# DDM_FOC_CostDown_Modify_X1_4.net
KiCad netlist of a schematic drawn in Altium Designer
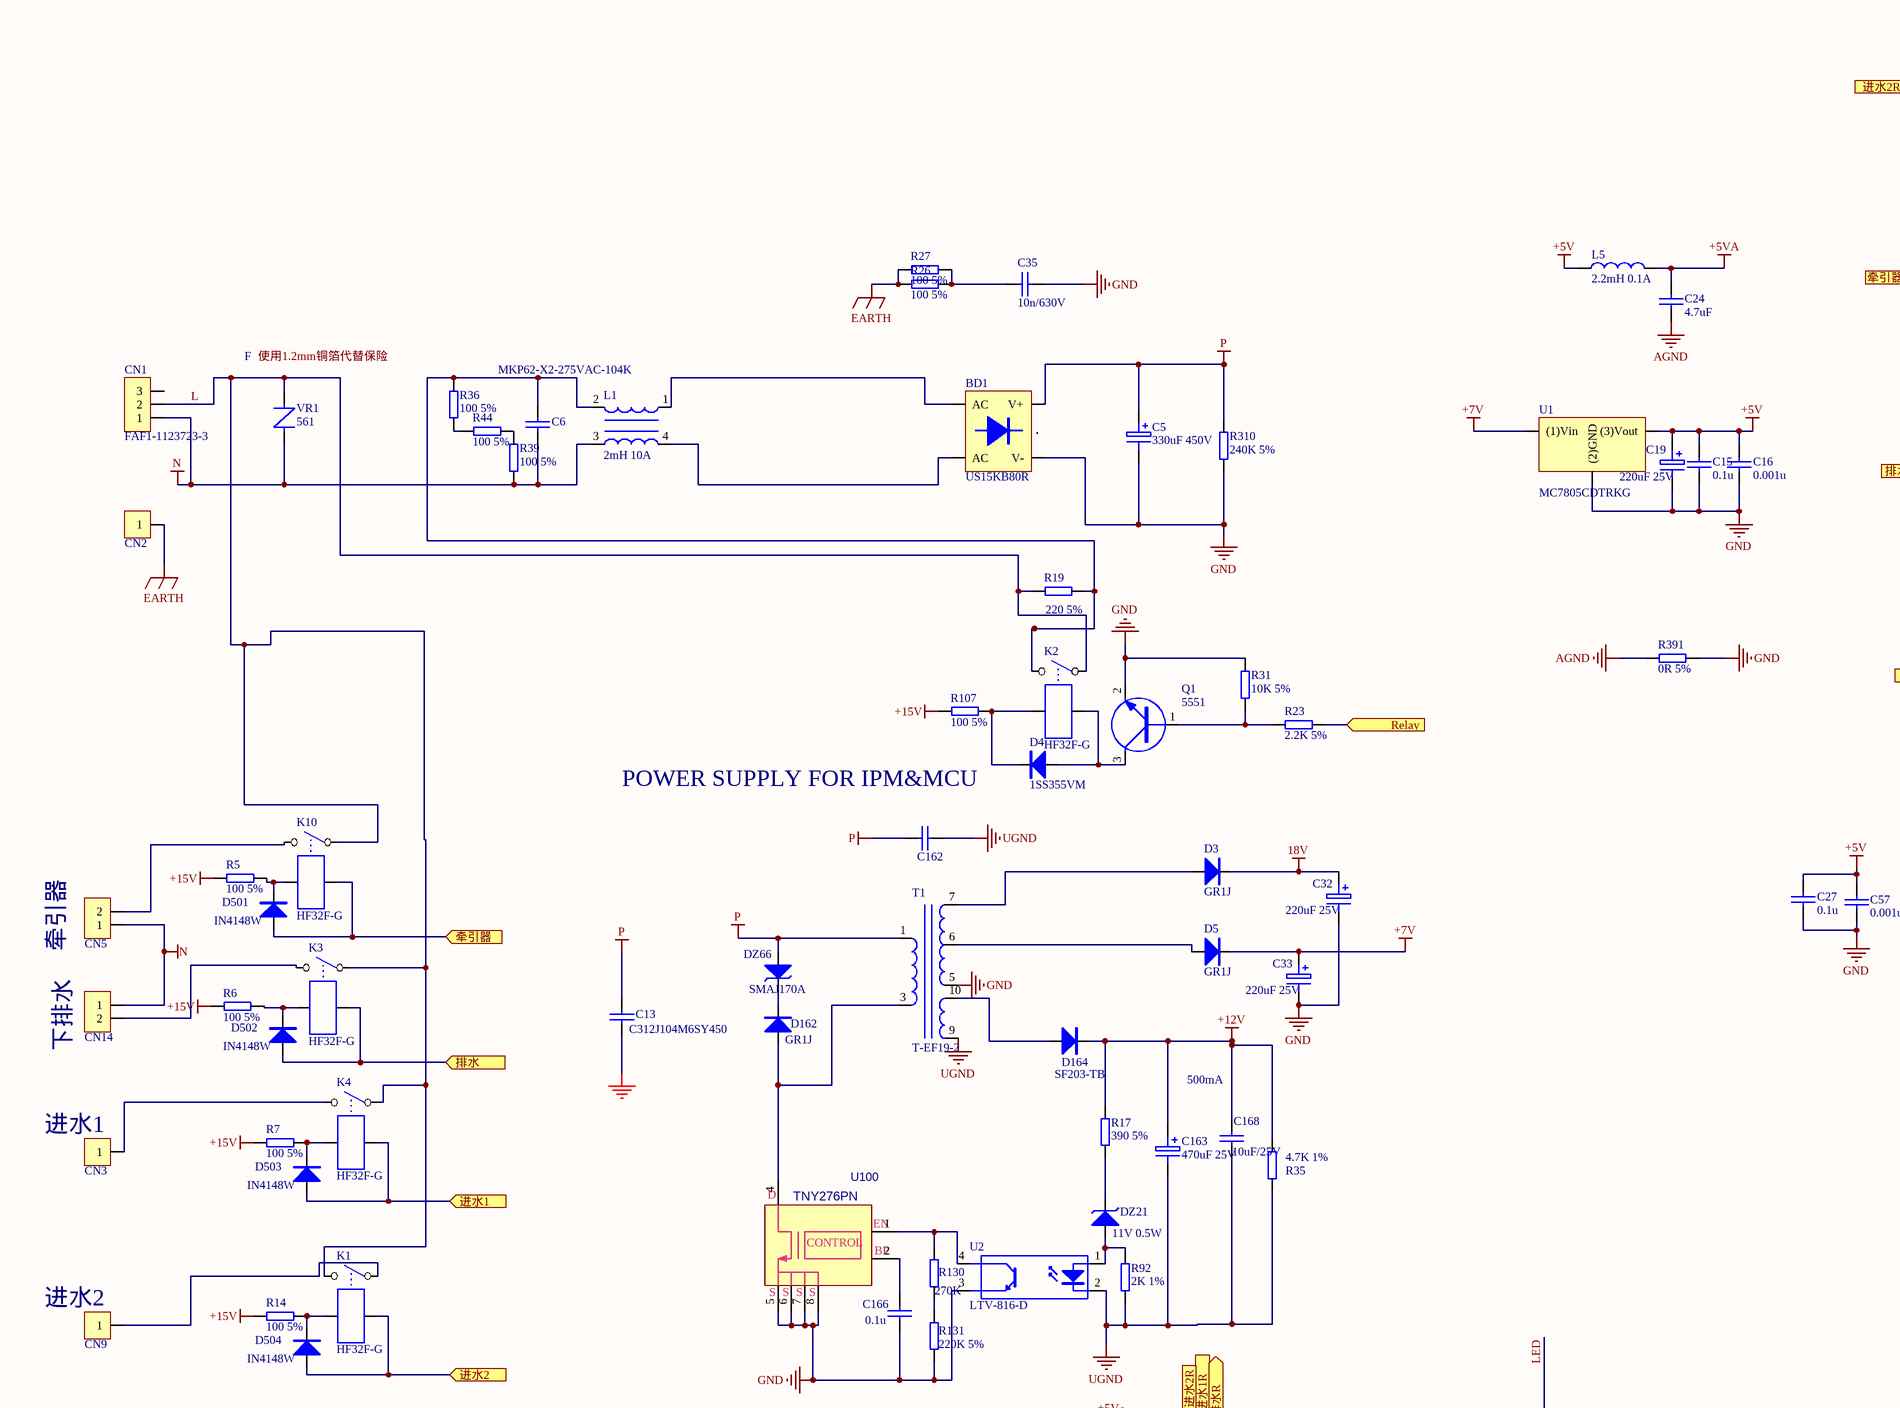
[diagram p0: DDM_FOC_CostDown_Modify_X1.4.schdoc, top left]
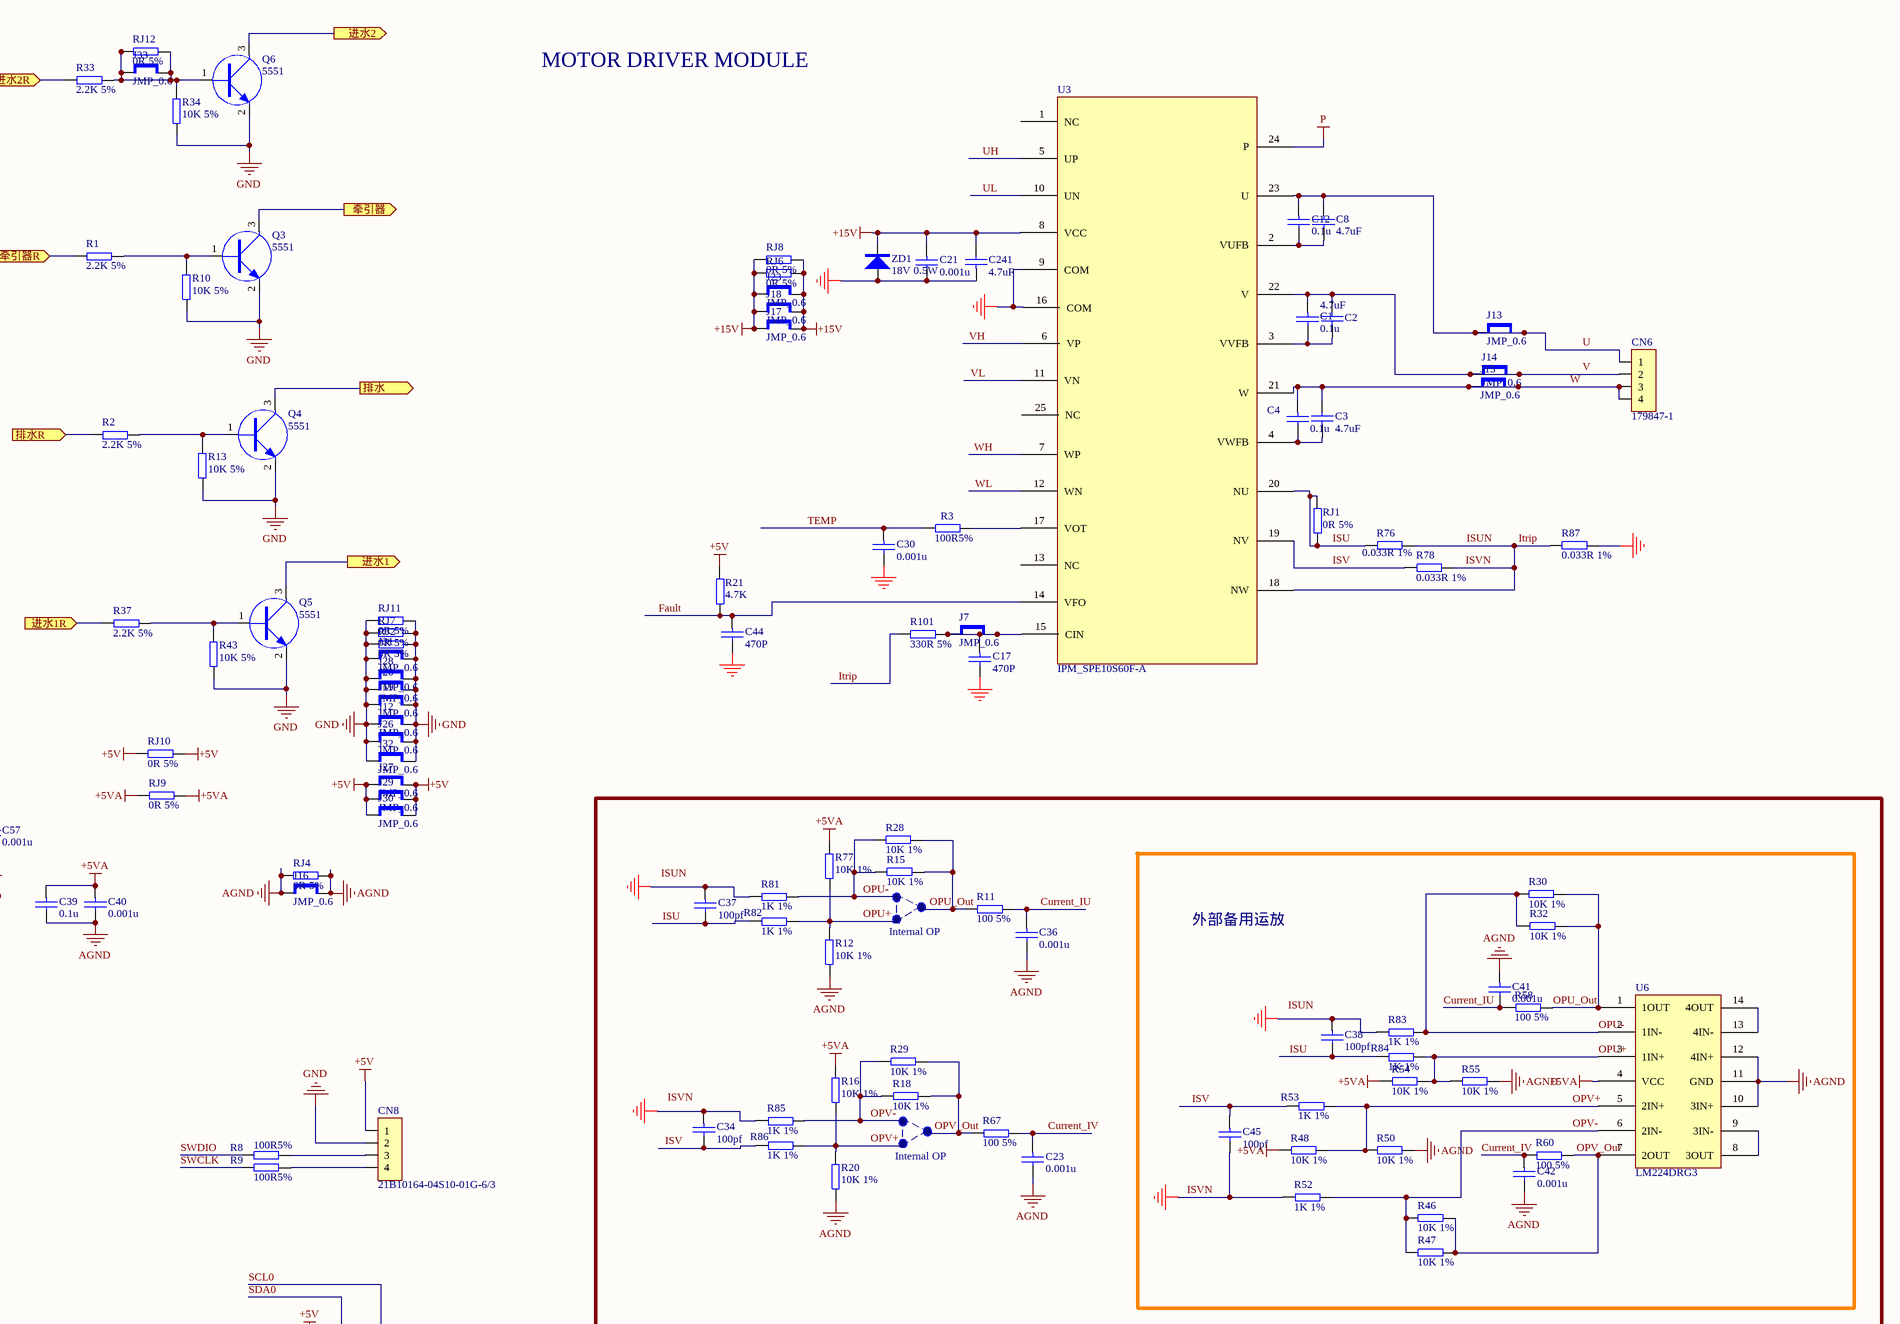
[diagram p1: DDM_FOC_CostDown_Modify_X1.4.schdoc, top right]
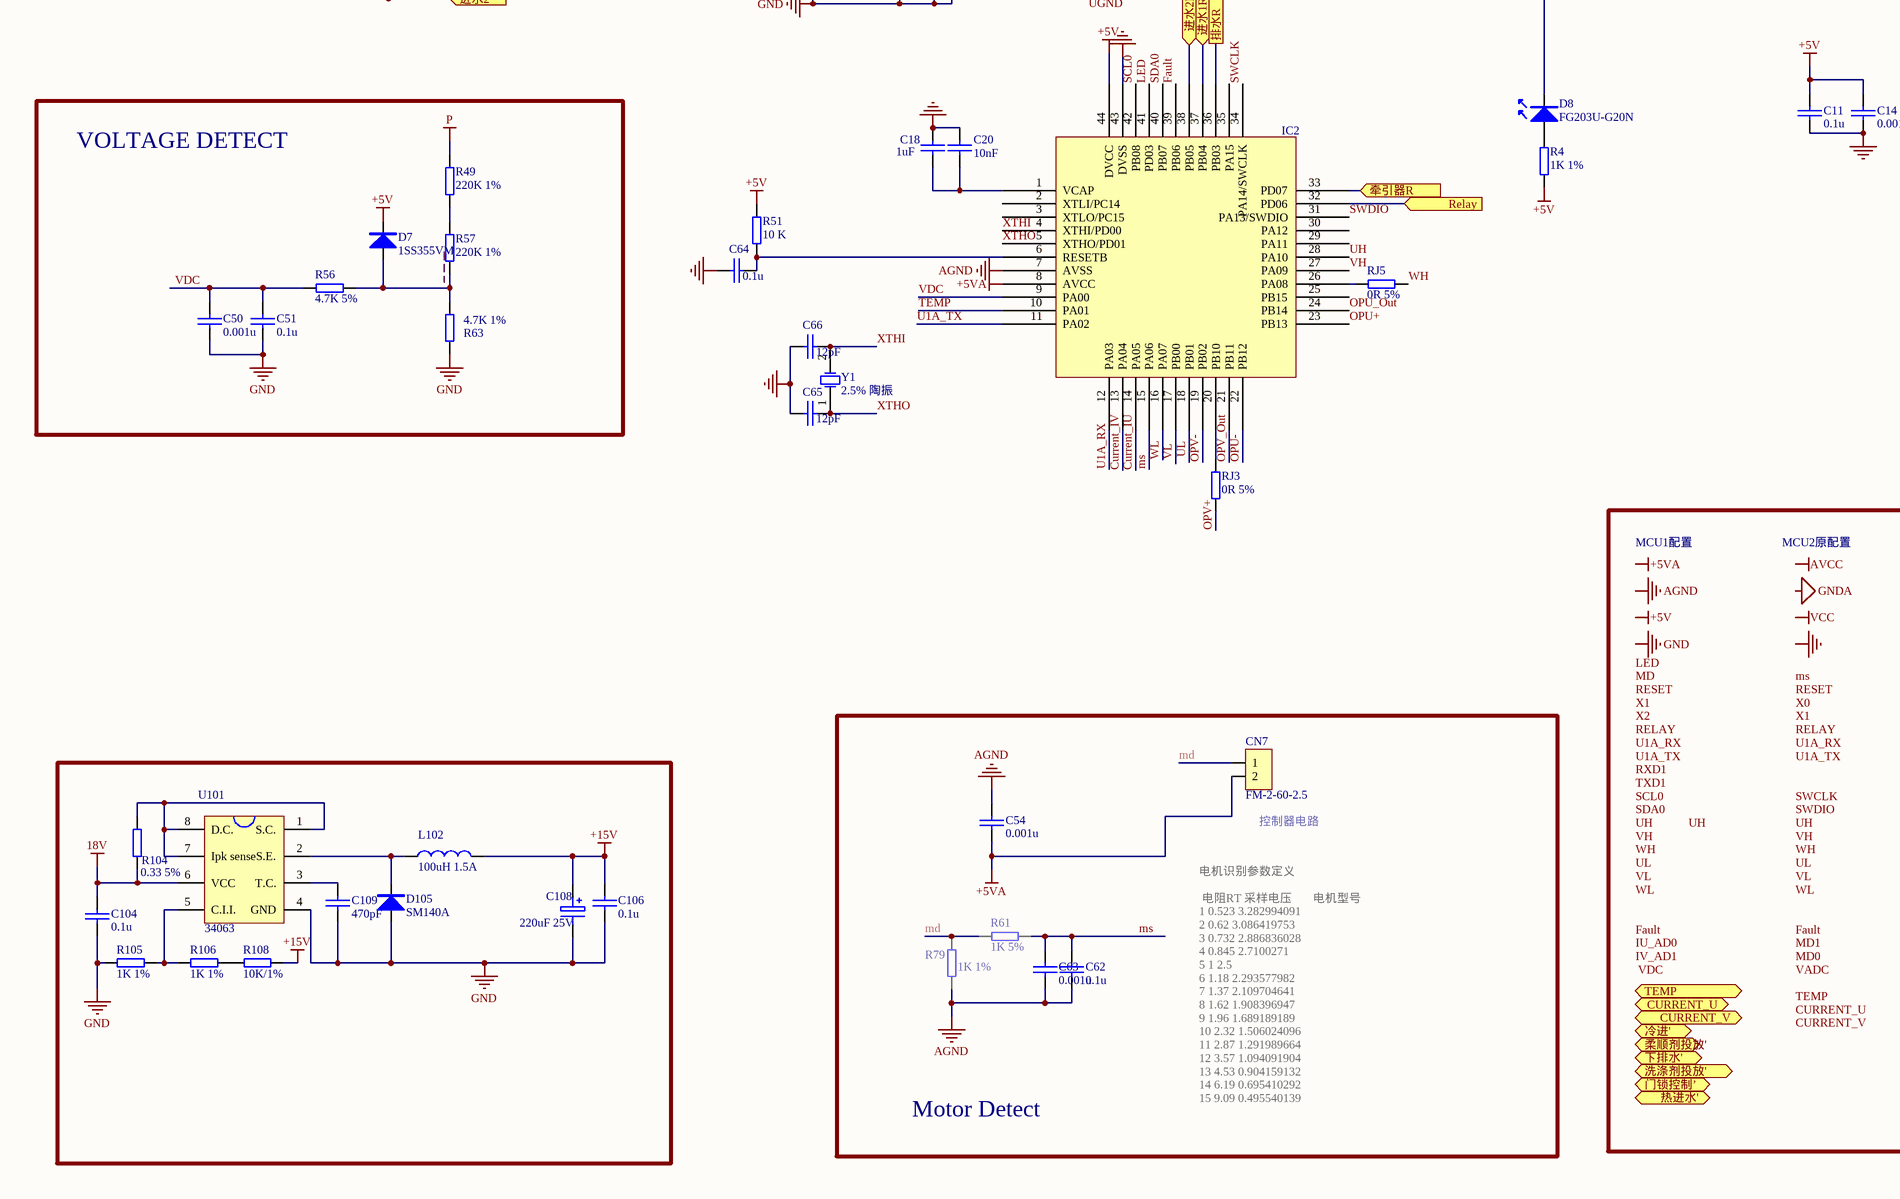
[diagram p2: DDM_FOC_CostDown_Modify_X1.4.schdoc, bottom left]
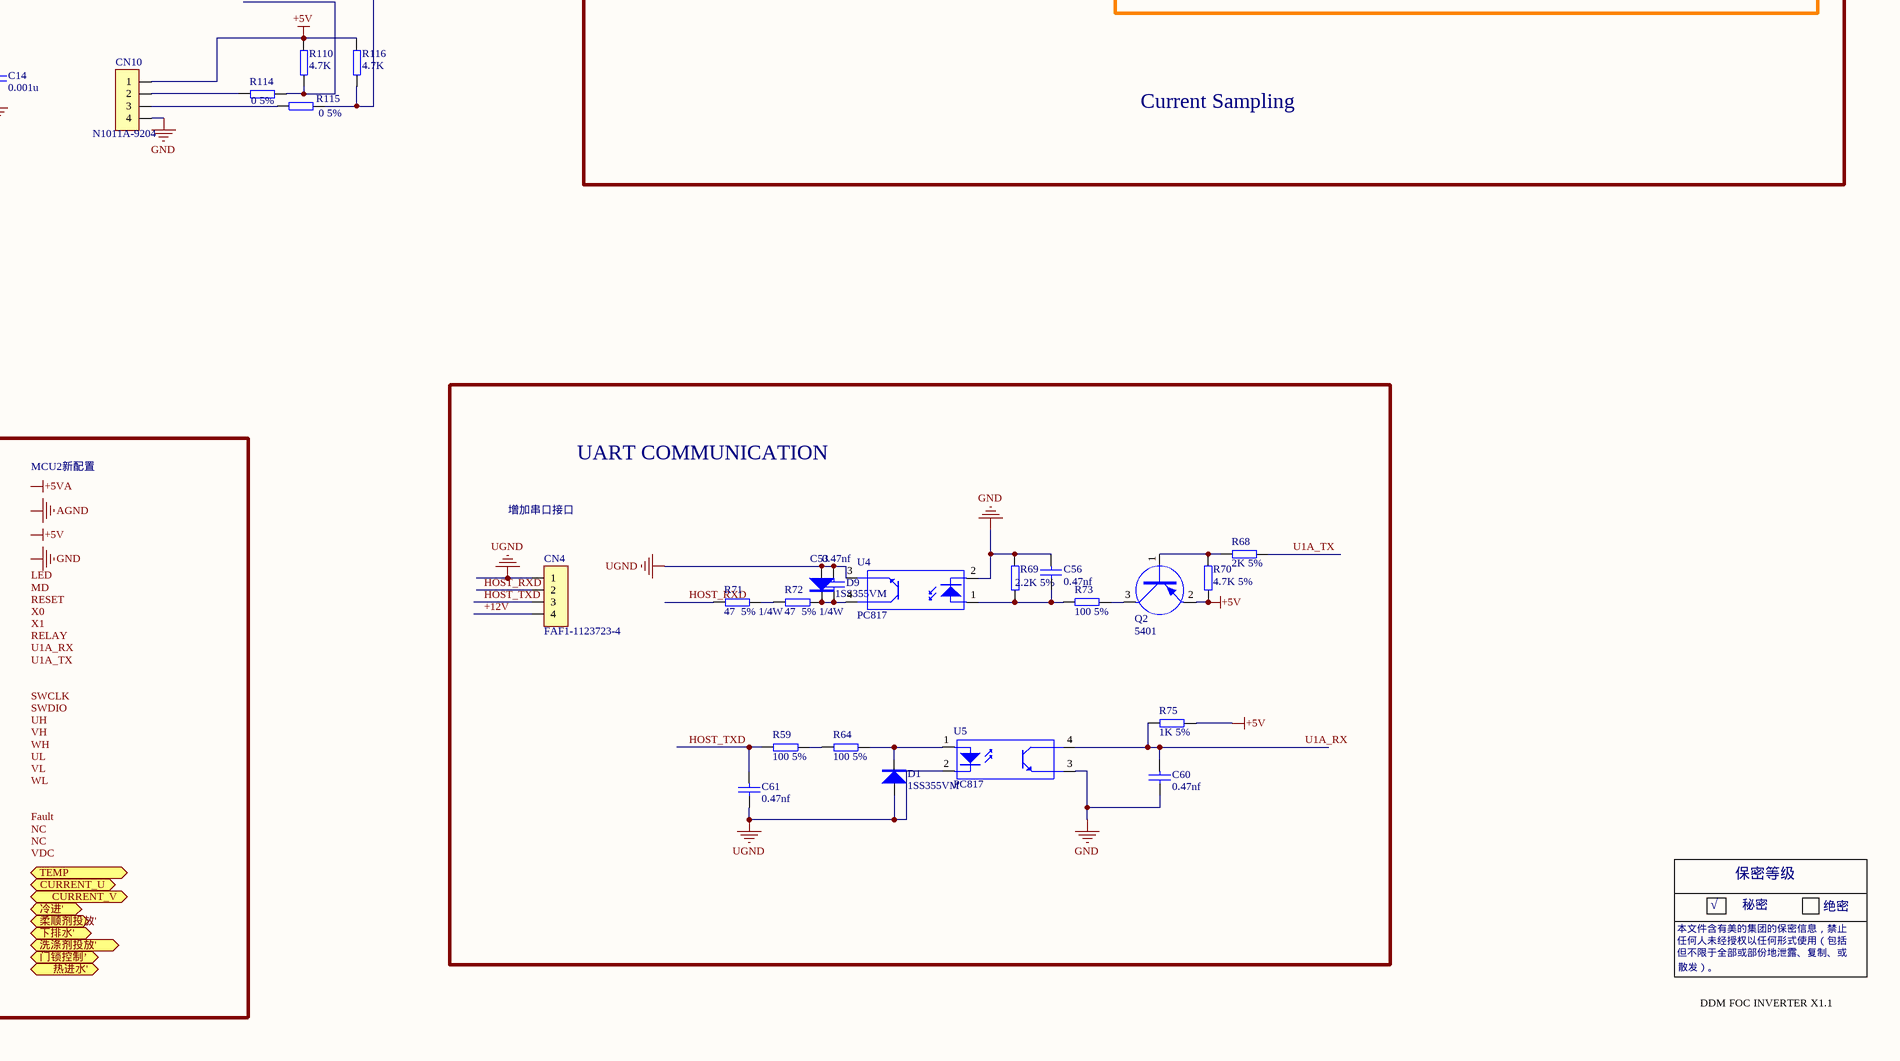
[diagram p3: DDM_FOC_CostDown_Modify_X1.4.schdoc, bottom right]

(export (version "E")
  (design (tool "Eeschema 10.0.6"))
  (components
    (comp (ref "BD1")
      (value "US15KB80R")
      (footprint "BD/D6K")
      (description "整流桥")
      (libsource (lib "sch") (part "BD_15A/800V"))
    )
    (comp (ref "C1")
      (value "0.1u")
      (footprint "C/0603")
      (description "贴片电容")
      (libsource (lib "sch") (part "C_SMD0805_104/50V_10%_X7R"))
    )
    (comp (ref "C2")
      (value "4.7uF")
      (footprint "C/1206")
      (description "瓷片电容")
      (libsource (lib "pre_sch") (part "C_SMD1206_475/25V_10%_X7R"))
    )
    (comp (ref "C3")
      (value "4.7uF")
      (footprint "C/1206")
      (description "瓷片电容")
      (libsource (lib "pre_sch") (part "C_SMD1206_475/25V_10%_X7R"))
    )
    (comp (ref "C4")
      (value "0.1u")
      (footprint "C/0603")
      (description "贴片电容")
      (libsource (lib "sch") (part "C_SMD0805_104/50V_10%_X7R"))
    )
    (comp (ref "C5")
      (value "330uF 450V")
      (footprint "E/10/35")
      (description "电解电容")
      (libsource (lib "pre_sch") (part "E_330UF/450V_85C_1"))
    )
    (comp (ref "C6")
      (value "MKP62-X2-275VAC-104K")
      (footprint "C/15/18*8.5")
      (description "薄膜电容")
      (libsource (lib "sch") (part "C_104/AC275V_10%_X2"))
    )
    (comp (ref "C8")
      (value "4.7uF")
      (footprint "C/1206")
      (description "瓷片电容")
      (libsource (lib "pre_sch") (part "C_SMD1206_475/25V_10%_X7R"))
    )
    (comp (ref "C11")
      (value "0.1u")
      (footprint "C/0603")
      (description "贴片电容")
      (libsource (lib "sch") (part "C_SMD0805_104/50V_10%_X7R"))
    )
    (comp (ref "C12")
      (value "0.1u")
      (footprint "C/0603")
      (description "贴片电容")
      (libsource (lib "sch") (part "C_SMD0805_104/50V_10%_X7R"))
    )
    (comp (ref "C13")
      (value "C312J104M6SY450")
      (footprint "C/15 /17.5*7.6")
      (description "薄膜电容C312J104M6SY450")
      (libsource (lib "pre_sch") (part "C_104/630V_5%_FILM"))
    )
    (comp (ref "C14")
      (value "0.001u")
      (footprint "C/0603")
      (description "贴片电容")
      (libsource (lib "sch") (part "C_SMD0805_104/50V_10%_X7R"))
    )
    (comp (ref "C15")
      (value "0.1u")
      (footprint "C/0603")
      (description "贴片电容")
      (libsource (lib "sch") (part "C_SMD0805_104/50V_10%_X7R"))
    )
    (comp (ref "C16")
      (value "0.001u")
      (footprint "C/0603")
      (description "贴片电容")
      (libsource (lib "sch") (part "C_SMD0805_104/50V_10%_X7R"))
    )
    (comp (ref "C17")
      (value "470P")
      (footprint "C/0603")
      (description "瓷片电容")
      (libsource (lib "sch") (part "C_SMD0603_102/50V_10%_X7R"))
    )
    (comp (ref "C18")
      (value "1uF")
      (footprint "C0603")
      (description "Ceramic Capacitor,0603")
      (libsource (lib "MyLib_Altium") (part "CAP-CC(SMD)"))
    )
    (comp (ref "C19")
      (value "220uF 25V")
      (footprint "E/5/8-@")
      (description "电解电容")
      (libsource (lib "sch") (part "E_220UF/25V_105C_L"))
    )
    (comp (ref "C20")
      (value "10nF")
      (footprint "C0603")
      (description "Ceramic Capacitor,0603")
      (libsource (lib "MyLib_Altium") (part "CAP-CC(SMD)"))
    )
    (comp (ref "C21")
      (value "0.001u")
      (footprint "C/0603")
      (description "贴片电容")
      (libsource (lib "sch") (part "C_SMD0805_104/50V_10%_X7R"))
    )
    (comp (ref "C23")
      (value "0.001u")
      (footprint "C/0603")
      (description "瓷片电容")
      (libsource (lib "sch") (part "C_SMD0603_102/50V_10%_X7R"))
    )
    (comp (ref "C24")
      (value "4.7uF")
      (footprint "C/0805")
      (description "瓷片电容")
      (libsource (lib "pre_sch") (part "C_SMD0805_475/16V_10%_X7R"))
    )
    (comp (ref "C27")
      (value "0.1u")
      (footprint "C/0603")
      (description "贴片电容")
      (libsource (lib "sch") (part "C_SMD0603_104/50V_10%_X7R"))
    )
    (comp (ref "C30")
      (value "0.001u")
      (footprint "C/0603")
      (description "瓷片电容")
      (libsource (lib "sch") (part "C_SMD0603_102/50V_10%_X7R"))
    )
    (comp (ref "C32")
      (value "220uF 25V")
      (footprint "E/5/8-@")
      (description "电解电容")
      (libsource (lib "sch") (part "E_220UF/25V_105C_L"))
    )
    (comp (ref "C33")
      (value "220uF 25V")
      (footprint "E/5/8-@")
      (description "电解电容")
      (libsource (lib "sch") (part "E_220UF/25V_105C_L"))
    )
    (comp (ref "C34")
      (value "100pf")
      (footprint "C/0603")
      (description "贴片电容")
      (libsource (lib "sch") (part "C_SMD0805_104/50V_10%_X7R"))
    )
    (comp (ref "C35")
      (value "10n/630V")
      (footprint "C/10/14.4*7")
      (description "薄膜电容")
      (libsource (lib "sch") (part "C_103/63V_10%_FILM"))
    )
    (comp (ref "C36")
      (value "0.001u")
      (footprint "C/0603")
      (description "瓷片电容")
      (libsource (lib "sch") (part "C_SMD0603_102/50V_10%_X7R"))
    )
    (comp (ref "C37")
      (value "100pf")
      (footprint "C/0603")
      (description "贴片电容")
      (libsource (lib "sch") (part "C_SMD0805_104/50V_10%_X7R"))
    )
    (comp (ref "C38")
      (value "100pf")
      (footprint "C/0603")
      (description "贴片电容")
      (libsource (lib "sch") (part "C_SMD0805_104/50V_10%_X7R"))
    )
    (comp (ref "C39")
      (value "0.1u")
      (footprint "C/0603")
      (description "贴片电容")
      (libsource (lib "sch") (part "C_SMD0805_104/50V_10%_X7R"))
    )
    (comp (ref "C40")
      (value "0.001u")
      (footprint "C/0603")
      (description "贴片电容")
      (libsource (lib "sch") (part "C_SMD0805_104/50V_10%_X7R"))
    )
    (comp (ref "C41")
      (value "0.001u")
      (footprint "C/0603")
      (description "瓷片电容")
      (libsource (lib "sch") (part "C_SMD0603_102/50V_10%_X7R"))
    )
    (comp (ref "C42")
      (value "0.001u")
      (footprint "C/0603")
      (description "瓷片电容")
      (libsource (lib "sch") (part "C_SMD0603_102/50V_10%_X7R"))
    )
    (comp (ref "C44")
      (value "470P")
      (footprint "C/0603")
      (description "贴片电容")
      (libsource (lib "sch") (part "C_SMD0805_104/50V_10%_X7R"))
    )
    (comp (ref "C45")
      (value "100pf")
      (footprint "C/0603")
      (description "贴片电容")
      (libsource (lib "sch") (part "C_SMD0805_104/50V_10%_X7R"))
    )
    (comp (ref "C50")
      (value "0.001u")
      (footprint "C/0603")
      (description "贴片电容")
      (libsource (lib "sch") (part "C_SMD0805_104/50V_10%_X7R"))
    )
    (comp (ref "C51")
      (value "0.1u")
      (footprint "C/0603")
      (description "贴片电容")
      (libsource (lib "sch") (part "C_SMD0805_104/50V_10%_X7R"))
    )
    (comp (ref "C53")
      (value "0.47nf")
      (footprint "C/0603")
      (description "瓷片电容")
      (libsource (lib "pre_sch") (part "C_SMD0603_471/50V_10%_X7R"))
    )
    (comp (ref "C54")
      (value "0.001u")
      (footprint "C/0603-SMT")
      (description "贴片电容")
      (libsource (lib "sch") (part "C_SMD0805_104/50V_10%_X7R"))
    )
    (comp (ref "C56")
      (value "0.47nf")
      (footprint "C/0603")
      (description "瓷片电容")
      (libsource (lib "pre_sch") (part "C_SMD0603_471/50V_10%_X7R"))
    )
    (comp (ref "C57")
      (value "0.001u")
      (footprint "C/0603")
      (description "贴片电容")
      (libsource (lib "sch") (part "C_SMD0805_104/50V_10%_X7R"))
    )
    (comp (ref "C60")
      (value "0.47nf")
      (footprint "C/0603")
      (description "瓷片电容")
      (libsource (lib "pre_sch") (part "C_SMD0603_471/50V_10%_X7R"))
    )
    (comp (ref "C61")
      (value "0.47nf")
      (footprint "C/0603-SMT")
      (description "瓷片电容")
      (libsource (lib "pre_sch") (part "C_SMD0603_471/50V_10%_X7R"))
    )
    (comp (ref "C62")
      (value "0.1u")
      (footprint "C/0603")
      (description "贴片电容")
      (libsource (lib "sch") (part "C_SMD0805_104/50V_10%_X7R"))
    )
    (comp (ref "C63")
      (value "0.001u")
      (footprint "C/0603-SMT")
      (description "贴片电容")
      (libsource (lib "sch") (part "C_SMD0805_104/50V_10%_X7R"))
    )
    (comp (ref "C64")
      (value "0.1u")
      (footprint "C/0603")
      (description "瓷片电容")
      (libsource (lib "*") (part "C_SMD0603_104/50V_10%_X7R"))
    )
    (comp (ref "C65")
      (value "12pF")
      (footprint "C/0603")
      (description "瓷片电容")
      (libsource (lib "*") (part "C_SMD0603_104/50V_10%_X7R"))
    )
    (comp (ref "C66")
      (value "12pF")
      (footprint "C/0603")
      (description "瓷片电容")
      (libsource (lib "*") (part "C_SMD0603_104/50V_10%_X7R"))
    )
    (comp (ref "C104")
      (value "0.1u")
      (footprint "C/0603")
      (description "贴片电容")
      (libsource (lib "SCH") (part "C_SMD0603_104/50V_10%_X7R"))
    )
    (comp (ref "C106")
      (value "0.1u")
      (footprint "C/0603")
      (description "贴片电容")
      (libsource (lib "SCH") (part "C_SMD0603_104/50V_10%_X7R"))
    )
    (comp (ref "C108")
      (value "220uF 25V")
      (footprint "E/5/8-@")
      (description "电解电容")
      (libsource (lib "sch") (part "E_220UF/25V_105C_L"))
    )
    (comp (ref "C109")
      (value "470pF")
      (footprint "C/0603")
      (description "贴片电容")
      (libsource (lib "SCH") (part "C_SMD0603_471/50V_10%"))
    )
    (comp (ref "C162")
      (value "CD12-E2GA471MYNS")
      (footprint "C/10/14.4*7")
      (description "Y1电容")
      (libsource (lib "sch") (part "C_222/AC400V_20%_Y1"))
    )
    (comp (ref "C163")
      (value "470uF 25V")
      (footprint "E/5/10-@")
      (description "电解电容")
      (libsource (lib "sch1") (part "E_470UF/25V_105C_L"))
    )
    (comp (ref "C166")
      (value "0.1u")
      (footprint "C/0603")
      (description "瓷片电容")
      (libsource (lib "sch") (part "C_SMD0603_104/50V_10%_X7R"))
    )
    (comp (ref "C168")
      (value "10uF/25V")
      (footprint "C/0805")
      (description "瓷片电容")
      (libsource (lib "sch") (part "C_SMD0805_105/25V_10%_X7R"))
    )
    (comp (ref "C241")
      (value "4.7uF")
      (footprint "C/0805")
      (description "瓷片电容")
      (libsource (lib "pre_sch") (part "C_SMD0805_475/16V_10%_X7R"))
    )
    (comp (ref "CN1")
      (value "FAF1-1123723-3")
      (footprint "CN/7.92/2")
      (description "3针插座")
      (libsource (lib "sch") (part "CN_3.96_3"))
    )
    (comp (ref "CN2")
      (value "CDW2.36-1P YE")
      (footprint "CN/CDW2.1-1P")
      (description "1针黄色插座")
      (libsource (lib "sch") (part "CN_1_01"))
    )
    (comp (ref "CN3")
      (value "CDW2.36-1P YE")
      (footprint "CN/CDW2.1-1P")
      (description "1针黄色插座")
      (libsource (lib "sch") (part "CN_1_01"))
    )
    (comp (ref "CN4")
      (value "FAF1-1123723-4")
      (footprint "CN/2.5/4-8 - 1")
      (description "4针插座")
      (libsource (lib "sch") (part "CN_3.96_4"))
    )
    (comp (ref "CN5")
      (value "PA1010")
      (footprint "CN/XH-2.1-2A")
      (description "2针插座")
      (libsource (lib "") (part "CN_8_2_05_1"))
    )
    (comp (ref "CN6")
      (value "179847-1")
      (footprint "CN/6.5/3/01")
      (description "4针插座")
      (libsource (lib "pre_sch") (part "CN_6.5_4_01"))
    )
    (comp (ref "CN7")
      (value "FM-2-60-2.5")
      (footprint "CN/2.5/2-3")
      (description "线束")
      (libsource (lib "sch") (part "CN_2.5_2"))
    )
    (comp (ref "CN8")
      (value "21B10164-04S10-01G-6/3")
      (footprint "CN/2.54/4")
      (description "单排排针4PIN")
      (libsource (lib "sch") (part "CN_2.54_4"))
    )
    (comp (ref "CN9")
      (value "CDW2.36-1P YE")
      (footprint "CN/CDW2.1-1P")
      (description "1针黄色插座")
      (libsource (lib "sch") (part "CN_1_01"))
    )
    (comp (ref "CN10")
      (value "N1011A-9204")
      (footprint "CN/2.54/4")
      (description "4针插座")
      (libsource (lib "pre_sch") (part "CN_2.5_4_6"))
    )
    (comp (ref "CN14")
      (value "PA1010")
      (footprint "CN/XH-2.1-2A")
      (description "2针插座")
      (libsource (lib "sch") (part "CN_8_2_05"))
    )
    (comp (ref "D1")
      (value "1SS355VM")
      (footprint "D/SOD-123")
      (description "贴片塑封二极管")
      (libsource (lib "pre_sch") (part "D_SMD_1SS355VM"))
    )
    (comp (ref "D3")
      (value "GR1J")
      (footprint "D/DO214AC")
      (description "二极管")
      (libsource (lib "sch1") (part "D_SMD_GR1J"))
    )
    (comp (ref "D4")
      (value "1SS355VM")
      (footprint "SOD/323")
      (description "贴片塑封二极管")
      (libsource (lib "pre_sch") (part "D_SMD_1SS355VM"))
    )
    (comp (ref "D5")
      (value "GR1J")
      (footprint "D/DO214AC")
      (description "二极管")
      (libsource (lib "sch1") (part "D_SMD_GR1J"))
    )
    (comp (ref "D7")
      (value "1SS355VM")
      (footprint "SOD/323")
      (description "贴片塑封二极管")
      (libsource (lib "pre_sch") (part "D_SMD_1SS355VM"))
    )
    (comp (ref "D8")
      (value "FG203U-G20N")
      (footprint "LED/2.54/Φ3-@")
      (description "插件发光二极管")
      (libsource (lib "sch") (part "LED_FG203U-G20N"))
    )
    (comp (ref "D9")
      (value "1SS355VM")
      (footprint "D/SOD-123")
      (description "贴片塑封二极管")
      (libsource (lib "pre_sch") (part "D_SMD_1SS355VM"))
    )
    (comp (ref "D105")
      (value "SM140A")
      (footprint "D/DO214AC")
      (description "肖特基二极管")
      (libsource (lib "pre_sch-5.11") (part "D_SMD_SM140A"))
    )
    (comp (ref "D162")
      (value "GR1J")
      (footprint "D/DO214AC")
      (description "二极管")
      (libsource (lib "sch1") (part "D_SMD_GR1J"))
    )
    (comp (ref "D164")
      (value "SF203-TB")
      (footprint "D/DO214AC")
      (description "二极管")
      (libsource (lib "sch1") (part "D_STTH1R02QRL"))
    )
    (comp (ref "D501")
      (value "IN4148W")
      (footprint "D/SOD-123")
      (description "塑封贴片二极管")
      (libsource (lib "pre_sch") (part "D_SMD_IN4148W"))
    )
    (comp (ref "D502")
      (value "IN4148W")
      (footprint "D/SOD-123")
      (description "塑封贴片二极管")
      (libsource (lib "pre_sch") (part "D_SMD_IN4148W"))
    )
    (comp (ref "D503")
      (value "IN4148W")
      (footprint "D/SOD-123")
      (description "塑封贴片二极管")
      (libsource (lib "pre_sch") (part "D_SMD_IN4148W"))
    )
    (comp (ref "D504")
      (value "IN4148W")
      (footprint "D/SOD-123")
      (description "塑封贴片二极管")
      (libsource (lib "pre_sch") (part "D_SMD_IN4148W"))
    )
    (comp (ref "DZ21")
      (value "11V 0.5W")
      (footprint "D/SOD80")
      (description "稳压二极管")
      (libsource (lib "sch1") (part "DZ_SMD_11V/0.5W"))
    )
    (comp (ref "DZ66")
      (value "SMAJ170A")
      (footprint "D/DO214AC")
      (description "TVS")
      (libsource (lib "sch1") (part "D_SMD_SMAJ170A"))
    )
    (comp (ref "IC2") (value "HC32F030") (libsource (lib "LQFP44") (part "HC32F030H8TA_LQFP44")))
    (comp (ref "J7")
      (value "JMP_0.6")
      (footprint "J/10-@")
      (description "跳线")
      (libsource (lib "sch") (part "J_D0.6"))
    )
    (comp (ref "J12")
      (value "JMP_0.6")
      (footprint "J/7-@")
      (description "跳线")
      (libsource (lib "sch") (part "J_D0.6"))
    )
    (comp (ref "J13")
      (value "JMP_0.6")
      (footprint "J/14-@")
      (description "跳线")
      (libsource (lib "sch") (part "J_D0.6"))
    )
    (comp (ref "J14")
      (value "JMP_0.6")
      (footprint "J/14-@")
      (description "跳线")
      (libsource (lib "sch") (part "J_D0.6"))
    )
    (comp (ref "J15")
      (value "JMP_0.6")
      (footprint "J/16-@")
      (description "跳线")
      (libsource (lib "sch") (part "J_D0.6"))
    )
    (comp (ref "J16")
      (value "JMP_0.6")
      (footprint "J/9-@")
      (description "跳线")
      (libsource (lib "sch") (part "J_D0.6"))
    )
    (comp (ref "J17")
      (value "JMP_0.6")
      (footprint "J/8-@")
      (description "跳线")
      (libsource (lib "sch") (part "J_D0.6"))
    )
    (comp (ref "J18")
      (value "JMP_0.6")
      (footprint "J/6-@")
      (description "跳线")
      (libsource (lib "sch") (part "J_D0.6"))
    )
    (comp (ref "J19")
      (value "JMP_0.6")
      (footprint "J/15-@")
      (description "跳线")
      (libsource (lib "sch") (part "J_D0.6"))
    )
    (comp (ref "J20")
      (value "JMP_0.6")
      (footprint "J/17-@")
      (description "跳线")
      (libsource (lib "sch") (part "J_D0.6"))
    )
    (comp (ref "J23")
      (value "JMP_0.6")
      (footprint "J/18-@")
      (description "跳线")
      (libsource (lib "sch") (part "J_D0.6"))
    )
    (comp (ref "J26")
      (value "JMP_0.6")
      (footprint "J/9-@")
      (description "跳线")
      (libsource (lib "sch") (part "J_D0.6"))
    )
    (comp (ref "J27")
      (value "JMP_0.6")
      (footprint "J/9-@")
      (description "跳线")
      (libsource (lib "sch") (part "J_D0.6"))
    )
    (comp (ref "J28")
      (value "JMP_0.6")
      (footprint "J/12-@")
      (description "跳线")
      (libsource (lib "sch") (part "J_D0.6"))
    )
    (comp (ref "J29")
      (value "JMP_0.6")
      (footprint "J/7-@")
      (description "跳线")
      (libsource (lib "sch") (part "J_D0.6"))
    )
    (comp (ref "J30")
      (value "JMP_0.6")
      (footprint "J/8-@")
      (description "跳线")
      (libsource (lib "sch") (part "J_D0.6"))
    )
    (comp (ref "J31")
      (value "JMP_0.6")
      (footprint "J/7-@")
      (description "跳线")
      (libsource (lib "sch") (part "J_D0.6"))
    )
    (comp (ref "J32")
      (value "JMP_0.6")
      (footprint "J/12-@")
      (description "跳线")
      (libsource (lib "sch") (part "J_D0.6"))
    )
    (comp (ref "J33")
      (value "JMP_0.6")
      (footprint "J/6-@")
      (description "跳线")
      (libsource (lib "sch") (part "J_D0.6"))
    )
    (comp (ref "K1")
      (value "HF32F-G")
      (footprint "RY/HF32")
      (description "继电器")
      (libsource (lib "sch") (part "RY_SPST_HF32F-G/012-HS"))
    )
    (comp (ref "K2")
      (value "HF32F-G")
      (footprint "RY/HF32")
      (description "继电器")
      (libsource (lib "sch") (part "RY_SPST_HF32F-G/012-HS"))
    )
    (comp (ref "K3")
      (value "HF32F-G")
      (footprint "RY/HF32")
      (description "继电器")
      (libsource (lib "sch") (part "RY_SPST_HF32F-G/012-HS"))
    )
    (comp (ref "K4")
      (value "HF32F-G")
      (footprint "RY/HF32")
      (description "继电器")
      (libsource (lib "sch") (part "RY_SPST_HF32F-G/012-HS"))
    )
    (comp (ref "K10")
      (value "HF32F-G")
      (footprint "RY/HF32")
      (description "继电器")
      (libsource (lib "sch") (part "RY_SPST_HF32F-G/012-HS"))
    )
    (comp (ref "L1")
      (value "2mH 10A")
      (footprint "L/18*21")
      (description "电感")
      (libsource (lib "pre_sch") (part "L_10A_2MH"))
    )
    (comp (ref "L5")
      (value "2.2mH 0.1A")
      (footprint "L/15/0410@")
      (description "电感")
      (libsource (lib "pre_sch") (part "L_0.1A_1MH"))
    )
    (comp (ref "L102")
      (value "100uH 1.5A")
      (footprint "L/5/11")
      (description "电感")
      (libsource (lib "pre_sch-5.11") (part "L_1.5A_100uH"))
    )
    (comp (ref "Q1")
      (value "5551")
      (footprint "Q/SOT23")
      (description "三极管")
      (libsource (lib "sch") (part "Q_N_MMBT5551_SOT23"))
    )
    (comp (ref "Q2")
      (value "5401")
      (footprint "Q/SOT23")
      (description "三极管")
      (libsource (lib "sch") (part "Q_P_MMBT5401_SOT23"))
    )
    (comp (ref "Q3")
      (value "5551")
      (footprint "Q/SOT23")
      (description "三极管")
      (libsource (lib "sch") (part "Q_N_MMBT5551_SOT23"))
    )
    (comp (ref "Q4")
      (value "5551")
      (footprint "Q/SOT23")
      (description "三极管")
      (libsource (lib "sch") (part "Q_N_MMBT5551_SOT23"))
    )
    (comp (ref "Q5")
      (value "5551")
      (footprint "Q/SOT23")
      (description "三极管")
      (libsource (lib "sch") (part "Q_N_MMBT5551_SOT23"))
    )
    (comp (ref "Q6")
      (value "5551")
      (footprint "Q/SOT23")
      (description "三极管")
      (libsource (lib "sch") (part "Q_N_MMBT5551_SOT23"))
    )
    (comp (ref "R1")
      (value "2.2K 5%")
      (footprint "R/0805")
      (description "电阻")
      (libsource (lib "sch") (part "R_SMD_0805_2.2K"))
    )
    (comp (ref "R2")
      (value "2.2K 5%")
      (footprint "R/0805")
      (description "电阻")
      (libsource (lib "sch") (part "R_SMD_0805_2.2K"))
    )
    (comp (ref "R3")
      (value "100R5%")
      (footprint "R/0805")
      (description "电阻")
      (libsource (lib "sch") (part "R_SMD_1206_0R"))
    )
    (comp (ref "R4")
      (value "1K 1%")
      (footprint "R/0805")
      (description "贴片电阻")
      (libsource (lib "sch") (part "R_SMD_0805_1K_1%"))
    )
    (comp (ref "R5")
      (value "100 5%")
      (footprint "R/1206")
      (description "电阻")
      (libsource (lib "sch") (part "R_SMD_1206_100"))
    )
    (comp (ref "R6")
      (value "100 5%")
      (footprint "R/1206")
      (description "电阻")
      (libsource (lib "sch") (part "R_SMD_1206_100"))
    )
    (comp (ref "R7")
      (value "100 5%")
      (footprint "R/1206")
      (description "电阻")
      (libsource (lib "sch") (part "R_SMD_1206_100"))
    )
    (comp (ref "R8")
      (value "100R5%")
      (footprint "R/0805")
      (description "电阻")
      (libsource (lib "sch") (part "R_SMD_1206_0R"))
    )
    (comp (ref "R9")
      (value "100R5%")
      (footprint "R/0805")
      (description "电阻")
      (libsource (lib "sch") (part "R_SMD_1206_0R"))
    )
    (comp (ref "R10")
      (value "10K 5%")
      (footprint "R/0805")
      (description "电阻")
      (libsource (lib "sch") (part "R_SMD_0805_10K"))
    )
    (comp (ref "R11")
      (value "100 5%")
      (footprint "R/0805")
      (description "贴片电阻")
      (libsource (lib "sch") (part "R_SMD_0805_100"))
    )
    (comp (ref "R12")
      (value "10K 1%")
      (footprint "R/0805")
      (description "电阻")
      (libsource (lib "sch") (part "R_SMD_0805_24.9K_1%"))
    )
    (comp (ref "R13")
      (value "10K 5%")
      (footprint "R/0805")
      (description "电阻")
      (libsource (lib "sch") (part "R_SMD_0805_10K"))
    )
    (comp (ref "R14")
      (value "100 5%")
      (footprint "R/1206")
      (description "电阻")
      (libsource (lib "sch") (part "R_SMD_1206_100"))
    )
    (comp (ref "R15")
      (value "10K 1%")
      (footprint "R/0805")
      (description "电阻")
      (libsource (lib "sch") (part "R_SMD_0805_24.9K_1%"))
    )
    (comp (ref "R16")
      (value "10K 1%")
      (footprint "R/0805")
      (description "电阻")
      (libsource (lib "sch") (part "R_SMD_0805_24.9K_1%"))
    )
    (comp (ref "R17")
      (value "390 5%")
      (footprint "R/1206")
      (description "电阻")
      (libsource (lib "sch") (part "R_SMD_1206_330"))
    )
    (comp (ref "R18")
      (value "10K 1%")
      (footprint "R/0805")
      (description "电阻")
      (libsource (lib "sch") (part "R_SMD_0805_24.9K_1%"))
    )
    (comp (ref "R19")
      (value "220 5%")
      (footprint "R/7.5/PTC")
      (description "电阻")
      (libsource (lib "pre_sch") (part "R_220_5%_2W"))
    )
    (comp (ref "R20")
      (value "10K 1%")
      (footprint "R/0805")
      (description "电阻")
      (libsource (lib "sch") (part "R_SMD_0805_24.9K_1%"))
    )
    (comp (ref "R21") (value "4.7K") (footprint "R/0805") (libsource (lib "*") (part "RES")))
    (comp (ref "R23")
      (value "2.2K 5%")
      (footprint "R/0805")
      (description "电阻")
      (libsource (lib "sch") (part "R_SMD_0805_2.2K"))
    )
    (comp (ref "R26")
      (value "100 5%")
      (footprint "R/1206")
      (description "电阻")
      (libsource (lib "sch") (part "R_SMD_1206_100"))
    )
    (comp (ref "R27")
      (value "100 5%")
      (footprint "R/1206")
      (description "电阻")
      (libsource (lib "sch") (part "R_SMD_1206_100"))
    )
    (comp (ref "R28")
      (value "10K 1%")
      (footprint "R/0805")
      (description "电阻")
      (libsource (lib "sch") (part "R_SMD_0805_24.9K_1%"))
    )
    (comp (ref "R29")
      (value "10K 1%")
      (footprint "R/0805")
      (description "电阻")
      (libsource (lib "sch") (part "R_SMD_0805_24.9K_1%"))
    )
    (comp (ref "R30")
      (value "10K 1%")
      (footprint "R/0805")
      (description "电阻")
      (libsource (lib "sch") (part "R_SMD_0805_24.9K_1%"))
    )
    (comp (ref "R31")
      (value "10K 5%")
      (footprint "R/0805")
      (description "电阻")
      (libsource (lib "sch") (part "R_SMD_0805_10K"))
    )
    (comp (ref "R32")
      (value "10K 1%")
      (footprint "R/0805")
      (description "电阻")
      (libsource (lib "sch") (part "R_SMD_0805_24.9K_1%"))
    )
    (comp (ref "R33")
      (value "2.2K 5%")
      (footprint "R/0805")
      (description "电阻")
      (libsource (lib "sch") (part "R_SMD_0805_2.2K"))
    )
    (comp (ref "R34")
      (value "10K 5%")
      (footprint "R/0805")
      (description "电阻")
      (libsource (lib "sch") (part "R_SMD_0805_10K"))
    )
    (comp (ref "R35")
      (value "4.7K 1%")
      (footprint "R/0805")
      (description "电阻")
      (libsource (lib "sch") (part "R_SMD_0805_2.43K_1%"))
    )
    (comp (ref "R36")
      (value "100 5%")
      (footprint "R/1206")
      (description "电阻")
      (libsource (lib "sch") (part "R_SMD_1206_100"))
    )
    (comp (ref "R37")
      (value "2.2K 5%")
      (footprint "R/0805")
      (description "电阻")
      (libsource (lib "sch") (part "R_SMD_0805_2.2K"))
    )
    (comp (ref "R39")
      (value "100 5%")
      (footprint "R/1206")
      (description "电阻")
      (libsource (lib "sch") (part "R_SMD_1206_100"))
    )
    (comp (ref "R43")
      (value "10K 5%")
      (footprint "R/0805")
      (description "电阻")
      (libsource (lib "sch") (part "R_SMD_0805_10K"))
    )
    (comp (ref "R44")
      (value "100 5%")
      (footprint "R/1206")
      (description "电阻")
      (libsource (lib "sch") (part "R_SMD_1206_100"))
    )
    (comp (ref "R46")
      (value "10K 1%")
      (footprint "R/0805")
      (description "电阻")
      (libsource (lib "sch") (part "R_SMD_0805_24.9K_1%"))
    )
    (comp (ref "R47")
      (value "10K 1%")
      (footprint "R/0805")
      (description "电阻")
      (libsource (lib "sch") (part "R_SMD_0805_24.9K_1%"))
    )
    (comp (ref "R48")
      (value "10K 1%")
      (footprint "R/0805")
      (description "电阻")
      (libsource (lib "sch") (part "R_SMD_0805_24.9K_1%"))
    )
    (comp (ref "R49")
      (value "220K 1%")
      (footprint "R/1206")
      (description "电阻")
      (libsource (lib "pre_sch") (part "R_SMD_1206_220K_1%"))
    )
    (comp (ref "R50")
      (value "10K 1%")
      (footprint "R/0805")
      (description "电阻")
      (libsource (lib "sch") (part "R_SMD_0805_24.9K_1%"))
    )
    (comp (ref "R51")
      (value "10 K")
      (footprint "R/0805")
      (description "电阻")
      (libsource (lib "*") (part "R_SMD_0805_3.3K"))
    )
    (comp (ref "R52")
      (value "1K 1%")
      (footprint "R/0805")
      (description "电阻")
      (libsource (lib "sch") (part "R_SMD_0805_3.09K_1%"))
    )
    (comp (ref "R53")
      (value "1K 1%")
      (footprint "R/0805")
      (description "电阻")
      (libsource (lib "sch") (part "R_SMD_0805_3.09K_1%"))
    )
    (comp (ref "R54")
      (value "10K 1%")
      (footprint "R/0805")
      (description "电阻")
      (libsource (lib "sch") (part "R_SMD_0805_24.9K_1%"))
    )
    (comp (ref "R55")
      (value "10K 1%")
      (footprint "R/0805")
      (description "电阻")
      (libsource (lib "sch") (part "R_SMD_0805_24.9K_1%"))
    )
    (comp (ref "R56")
      (value "4.7K 5%")
      (footprint "R/0805")
      (description "电阻")
      (libsource (lib "sch") (part "R_SMD_0805_4.7K"))
    )
    (comp (ref "R57")
      (value "220K 1%")
      (footprint "R/1206")
      (description "电阻")
      (libsource (lib "pre_sch") (part "R_SMD_1206_220K_1%"))
    )
    (comp (ref "R58")
      (value "100 5%")
      (footprint "R/0805")
      (description "贴片电阻")
      (libsource (lib "sch") (part "R_SMD_0805_100"))
    )
    (comp (ref "R59")
      (value "100 5%")
      (footprint "R/1206")
      (description "电阻")
      (libsource (lib "sch") (part "R_SMD_1206_100"))
    )
    (comp (ref "R60")
      (value "100 5%")
      (footprint "R/0805")
      (description "贴片电阻")
      (libsource (lib "sch") (part "R_SMD_0805_100"))
    )
    (comp (ref "R61")
      (value "1K 5%")
      (footprint "R/0805")
      (description "电阻")
      (libsource (lib "sch") (part "R_SMD_0805_1K"))
    )
    (comp (ref "R63")
      (value "4.7K 1%")
      (footprint "R/0805")
      (description "电阻")
      (libsource (lib "sch") (part "R_SMD_0805_2.43K_1%"))
    )
    (comp (ref "R64")
      (value "100 5%")
      (footprint "R/1206")
      (description "电阻")
      (libsource (lib "sch") (part "R_SMD_1206_100"))
    )
    (comp (ref "R67")
      (value "100 5%")
      (footprint "R/0805")
      (description "贴片电阻")
      (libsource (lib "sch") (part "R_SMD_0805_100"))
    )
    (comp (ref "R68")
      (value "2K 5%")
      (footprint "R/0805")
      (description "电阻")
      (libsource (lib "sch") (part "R_SMD_0805_2.2K"))
    )
    (comp (ref "R69")
      (value "2.2K 5%")
      (footprint "R/0805")
      (description "电阻")
      (libsource (lib "sch") (part "R_SMD_0805_2.2K"))
    )
    (comp (ref "R70")
      (value "4.7K 5%")
      (footprint "R/0805")
      (description "电阻")
      (libsource (lib "sch") (part "R_SMD_0805_4.7K"))
    )
    (comp (ref "R71")
      (value "47  5% 1/4W")
      (footprint "R/1206")
      (description "电阻")
      (libsource (lib "pre_sch") (part "R_SMD_1206_47"))
    )
    (comp (ref "R72")
      (value "47  5% 1/4W")
      (footprint "R/1206")
      (description "电阻")
      (libsource (lib "pre_sch") (part "R_SMD_1206_47"))
    )
    (comp (ref "R73")
      (value "100 5%")
      (footprint "R/1206")
      (description "电阻")
      (libsource (lib "sch") (part "R_SMD_1206_100"))
    )
    (comp (ref "R75")
      (value "1K 5%")
      (footprint "R/0805")
      (description "电阻")
      (libsource (lib "sch") (part "R_SMD_0805_330"))
    )
    (comp (ref "R76")
      (value "0.033R 1%")
      (footprint "R/2512")
      (description "电阻")
      (libsource (lib "pre_sch") (part "R_SMD_2512_150K"))
    )
    (comp (ref "R77")
      (value "10K 1%")
      (footprint "R/0805")
      (description "电阻")
      (libsource (lib "sch") (part "R_SMD_0805_24.9K_1%"))
    )
    (comp (ref "R78")
      (value "0.033R 1%")
      (footprint "R/2512")
      (description "电阻")
      (libsource (lib "pre_sch") (part "R_SMD_2512_150K"))
    )
    (comp (ref "R79")
      (value "1K 1%")
      (footprint "R/0805")
      (description "电阻")
      (libsource (lib "sch") (part "R_SMD_0805_1K"))
    )
    (comp (ref "R81")
      (value "1K 1%")
      (footprint "R/0805")
      (description "电阻")
      (libsource (lib "sch") (part "R_SMD_0805_3.09K_1%"))
    )
    (comp (ref "R82")
      (value "1K 1%")
      (footprint "R/0805")
      (description "电阻")
      (libsource (lib "sch") (part "R_SMD_0805_3.09K_1%"))
    )
    (comp (ref "R83")
      (value "1K 1%")
      (footprint "R/0805")
      (description "电阻")
      (libsource (lib "sch") (part "R_SMD_0805_3.09K_1%"))
    )
    (comp (ref "R84")
      (value "1K 1%")
      (footprint "R/0805")
      (description "电阻")
      (libsource (lib "sch") (part "R_SMD_0805_3.09K_1%"))
    )
    (comp (ref "R85")
      (value "1K 1%")
      (footprint "R/0805")
      (description "电阻")
      (libsource (lib "sch") (part "R_SMD_0805_3.09K_1%"))
    )
    (comp (ref "R86")
      (value "1K 1%")
      (footprint "R/0805")
      (description "电阻")
      (libsource (lib "sch") (part "R_SMD_0805_3.09K_1%"))
    )
    (comp (ref "R87")
      (value "0.033R 1%")
      (footprint "R/2512")
      (description "电阻")
      (libsource (lib "pre_sch") (part "R_SMD_2512_150K"))
    )
    (comp (ref "R92")
      (value "2K 1%")
      (footprint "R/0805")
      (description "电阻")
      (libsource (lib "sch") (part "R_SMD_0805_2K_1%"))
    )
    (comp (ref "R101")
      (value "330R 5%")
      (footprint "R/0805")
      (description "电阻")
      (libsource (lib "sch") (part "R_SMD_0805_1K_1%"))
    )
    (comp (ref "R104")
      (value "0.33 5%")
      (footprint "R/1206")
      (description "电阻")
      (libsource (lib "sch-5.11") (part "R_SMD_1206_330"))
    )
    (comp (ref "R105")
      (value "1K 1%")
      (footprint "R/0805")
      (description "电阻")
      (libsource (lib "sch") (part "R_SMD_0805_1K_1%"))
    )
    (comp (ref "R106")
      (value "1K 1%")
      (footprint "R/0805")
      (description "电阻")
      (libsource (lib "sch") (part "R_SMD_0805_1K_1%"))
    )
    (comp (ref "R107")
      (value "100 5%")
      (footprint "R/1206")
      (description "电阻")
      (libsource (lib "sch") (part "R_SMD_1206_100"))
    )
    (comp (ref "R108") (value "10K/1%") (footprint "R/0805") (libsource (lib "*") (part "RES")))
    (comp (ref "R110") (value "4.7K") (footprint "R/0805") (libsource (lib "*") (part "RES")))
    (comp (ref "R114") (value "0 5%") (footprint "R/0805") (libsource (lib "*") (part "RES")))
    (comp (ref "R115") (value "0 5%") (footprint "R/0805") (libsource (lib "*") (part "RES")))
    (comp (ref "R116") (value "4.7K") (footprint "R/0805") (libsource (lib "*") (part "RES")))
    (comp (ref "R130")
      (value "270K")
      (footprint "R/0805")
      (description "贴片电阻")
      (libsource (lib "sch") (part "R_SMD_0805_270K_1%"))
    )
    (comp (ref "R131")
      (value "220K 5%")
      (footprint "R/0805")
      (description "电阻")
      (libsource (lib "pre_sch") (part "R_SMD_0805_220K"))
    )
    (comp (ref "R310")
      (value "240K 5%")
      (footprint "R/2512")
      (description "电阻")
      (libsource (lib "sch") (part "R_SMD_0805_10K"))
    )
    (comp (ref "R391")
      (value "0R 5%")
      (footprint "J/1206")
      (description "电阻")
      (libsource (lib "sch") (part "R_SMD_1206_0R"))
    )
    (comp (ref "RJ1")
      (value "0R 5%")
      (footprint "J/1206")
      (description "贴片电阻")
      (libsource (lib "sch") (part "R_SMD_1206_0R"))
    )
    (comp (ref "RJ2")
      (value "0R 5%")
      (footprint "J/1206")
      (description "贴片电阻")
      (libsource (lib "sch") (part "R_SMD_1206_0R"))
    )
    (comp (ref "RJ3")
      (value "0R 5%")
      (footprint "J/1206")
      (description "贴片电阻")
      (libsource (lib "sch") (part "R_SMD_1206_0R"))
    )
    (comp (ref "RJ4")
      (value "0R 5%")
      (footprint "J/1206")
      (description "贴片电阻")
      (libsource (lib "sch") (part "R_SMD_1206_0R"))
    )
    (comp (ref "RJ5")
      (value "0R 5%")
      (footprint "J/1206")
      (description "贴片电阻")
      (libsource (lib "sch") (part "R_SMD_1206_0R"))
    )
    (comp (ref "RJ6")
      (value "0R 5%")
      (footprint "J/1206-1")
      (description "贴片电阻")
      (libsource (lib "sch") (part "R_SMD_1206_0R"))
    )
    (comp (ref "RJ7")
      (value "0R 5%")
      (footprint "J/1206-1")
      (description "贴片电阻")
      (libsource (lib "sch") (part "R_SMD_1206_0R"))
    )
    (comp (ref "RJ8")
      (value "0R 5%")
      (footprint "J/1206")
      (description "贴片电阻")
      (libsource (lib "sch") (part "R_SMD_1206_0R"))
    )
    (comp (ref "RJ9")
      (value "0R 5%")
      (footprint "J/1206")
      (description "贴片电阻")
      (libsource (lib "sch") (part "R_SMD_1206_0R"))
    )
    (comp (ref "RJ10")
      (value "0R 5%")
      (footprint "J/1206")
      (description "贴片电阻")
      (libsource (lib "sch") (part "R_SMD_1206_0R"))
    )
    (comp (ref "RJ11")
      (value "0R 5%")
      (footprint "J/1206-1")
      (description "贴片电阻")
      (libsource (lib "sch") (part "R_SMD_1206_0R"))
    )
    (comp (ref "RJ12")
      (value "0R 5%")
      (footprint "J/1206")
      (description "贴片电阻")
      (libsource (lib "sch") (part "R_SMD_1206_0R"))
    )
    (comp (ref "T1")
      (value "T-EF19-2")
      (footprint "T_EE19211 - 1")
      (libsource (lib "pre_sch00") (part "T-EF19-2"))
    )
    (comp (ref "U1")
      (value "MC7805CDTRKG")
      (footprint "IC/DPAK-3")
      (description "三端稳压器")
      (libsource (lib "pre_sch") (part "IC_PWR_MC7805CDTRKG"))
    )
    (comp (ref "U2")
      (value "LTV-816-D")
      (footprint "LTV-816S - @")
      (description "光耦")
      (libsource (lib "pre_sch") (part "IC_PS2501"))
    )
    (comp (ref "U3")
      (value "IPM_SPE10S60F-A")
      (footprint "IC_IPM_P")
      (libsource (lib "Schlib") (part "IPM_SPE10S60F-A"))
    )
    (comp (ref "U4")
      (value "PC817")
      (footprint "LTV-816S - @")
      (description "光耦")
      (libsource (lib "sch") (part "IC_OPTO_PC817X2NXZW"))
    )
    (comp (ref "U5")
      (value "PC817")
      (footprint "LTV-816S - @")
      (description "光耦")
      (libsource (lib "sch") (part "IC_OPTO_PC817X2NXZW"))
    )
    (comp (ref "U6") (value "LM224DRG3") (libsource (lib "op") (part "LM224DRG3")))
    (comp (ref "U100") (value "TNY276PN") (footprint "IC/DIP/7/3/8.5") (libsource (lib "*") (part "TNY27XP")))
    (comp (ref "U101")
      (value "34063")
      (footprint "IC/SOP/1.27/8/4-r")
      (description "电源IC")
      (libsource (lib "pre_sch-5.11") (part "IC_PWR_AZ34063U"))
    )
    (comp (ref "VR1")
      (value "561")
      (footprint "VR/5/15/7.5-@")
      (description "压敏电阻")
      (libsource (lib "sch") (part "VR_10D561"))
    )
    (comp (ref "Y1")
      (value "2.5% 陶振")
      (footprint "R38")
      (description "Crystal Oscillator")
      (fields (field (name "PUBLISHER") "Altium Limited"))
      (libsource (lib "Miscellaneous Devices") (part "XTAL"))
    )
    (comp (ref "ZD1")
      (value "18V 0.5W")
      (footprint "D/SOD80")
      (description "稳压二极管")
      (libsource (lib "sch") (part "DZ_SMD_18V/0.5W"))
    )
  )
  (nets
    (net (code "1") (name "+5V") (class "Default")
      (node (ref "C11") (pin "1") (pinfunction "1_1") (pintype "passive"))
      (node (ref "C14") (pin "1") (pinfunction "1_1") (pintype "passive"))
      (node (ref "C15") (pin "1") (pinfunction "1_1") (pintype "passive"))
      (node (ref "C16") (pin "1") (pinfunction "1_1") (pintype "passive"))
      (node (ref "C19") (pin "1") (pinfunction "1_1") (pintype "passive"))
      (node (ref "C27") (pin "1") (pinfunction "1_1") (pintype "passive"))
      (node (ref "C57") (pin "1") (pinfunction "1_1") (pintype "passive"))
      (node (ref "CN10") (pin "1") (pinfunction "1_1") (pintype "passive"))
      (node (ref "CN8") (pin "1") (pinfunction "1_1") (pintype "passive"))
      (node (ref "D7") (pin "2") (pinfunction "2_2") (pintype "passive"))
      (node (ref "IC2") (pin "44") (pinfunction "DVCC_44") (pintype "passive"))
      (node (ref "J27") (pin "1") (pinfunction "1_1") (pintype "passive"))
      (node (ref "J27") (pin "2") (pinfunction "2_2") (pintype "passive"))
      (node (ref "J29") (pin "1") (pinfunction "1_1") (pintype "passive"))
      (node (ref "J29") (pin "2") (pinfunction "2_2") (pintype "passive"))
      (node (ref "J30") (pin "1") (pinfunction "1_1") (pintype "passive"))
      (node (ref "J30") (pin "2") (pinfunction "2_2") (pintype "passive"))
      (node (ref "L5") (pin "1") (pinfunction "1_1") (pintype "passive"))
      (node (ref "Q2") (pin "2") (pinfunction "E_2") (pintype "passive"))
      (node (ref "R110") (pin "1") (pinfunction "1_1") (pintype "passive"))
      (node (ref "R116") (pin "1") (pinfunction "1_1") (pintype "passive"))
      (node (ref "R21") (pin "1") (pinfunction "1_1") (pintype "passive"))
      (node (ref "R4") (pin "2") (pinfunction "2_2") (pintype "passive"))
      (node (ref "R51") (pin "1") (pinfunction "1_1") (pintype "passive"))
      (node (ref "R70") (pin "2") (pinfunction "2_2") (pintype "passive"))
      (node (ref "R75") (pin "2") (pinfunction "2_2") (pintype "passive"))
      (node (ref "RJ10") (pin "1") (pinfunction "1_1") (pintype "passive"))
      (node (ref "RJ10") (pin "2") (pinfunction "2_2") (pintype "passive"))
      (node (ref "U1") (pin "3") (pinfunction "(3)Vout_3") (pintype "passive"))
    )
    (net (code "2") (name "+5VA") (class "Default")
      (node (ref "C24") (pin "2") (pinfunction "2_2") (pintype "passive"))
      (node (ref "C39") (pin "1") (pinfunction "1_1") (pintype "passive"))
      (node (ref "C40") (pin "1") (pinfunction "1_1") (pintype "passive"))
      (node (ref "C54") (pin "2") (pinfunction "2_2") (pintype "passive"))
      (node (ref "CN7") (pin "2") (pinfunction "2_2") (pintype "passive"))
      (node (ref "IC2") (pin "8") (pinfunction "AVCC_8") (pintype "passive"))
      (node (ref "L5") (pin "2") (pinfunction "2_2") (pintype "passive"))
      (node (ref "R16") (pin "2") (pinfunction "2_2") (pintype "passive"))
      (node (ref "R48") (pin "2") (pinfunction "2_2") (pintype "passive"))
      (node (ref "R54") (pin "2") (pinfunction "2_2") (pintype "passive"))
      (node (ref "R77") (pin "2") (pinfunction "2_2") (pintype "passive"))
      (node (ref "RJ9") (pin "1") (pinfunction "1_1") (pintype "passive"))
      (node (ref "RJ9") (pin "2") (pinfunction "2_2") (pintype "passive"))
      (node (ref "U6") (pin "4") (pinfunction "VCC_4") (pintype "passive"))
    )
    (net (code "3") (name "+7V") (class "Default")
      (node (ref "C33") (pin "1") (pinfunction "1_1") (pintype "passive"))
      (node (ref "D5") (pin "2") (pinfunction "K_2") (pintype "passive"))
      (node (ref "U1") (pin "1") (pinfunction "(1)Vin_1") (pintype "passive"))
    )
    (net (code "4") (name "+12V") (class "Default")
      (node (ref "C163") (pin "1") (pinfunction "1_1") (pintype "passive"))
      (node (ref "C168") (pin "1") (pinfunction "1_1") (pintype "passive"))
      (node (ref "CN4") (pin "4") (pinfunction "4_4") (pintype "passive"))
      (node (ref "D164") (pin "2") (pinfunction "K_2") (pintype "passive"))
      (node (ref "R17") (pin "2") (pinfunction "2_2") (pintype "passive"))
      (node (ref "R35") (pin "2") (pinfunction "2_2") (pintype "passive"))
    )
    (net (code "5") (name "+15V") (class "Default")
      (node (ref "C106") (pin "1") (pinfunction "1_1") (pintype "passive"))
      (node (ref "C108") (pin "1") (pinfunction "1_1") (pintype "passive"))
      (node (ref "C21") (pin "1") (pinfunction "1_1") (pintype "passive"))
      (node (ref "C241") (pin "2") (pinfunction "2_2") (pintype "passive"))
      (node (ref "J17") (pin "1") (pinfunction "1_1") (pintype "passive"))
      (node (ref "J17") (pin "2") (pinfunction "2_2") (pintype "passive"))
      (node (ref "J18") (pin "1") (pinfunction "1_1") (pintype "passive"))
      (node (ref "J18") (pin "2") (pinfunction "2_2") (pintype "passive"))
      (node (ref "J23") (pin "1") (pinfunction "1_1") (pintype "passive"))
      (node (ref "J23") (pin "2") (pinfunction "2_2") (pintype "passive"))
      (node (ref "L102") (pin "2") (pinfunction "2_2") (pintype "passive"))
      (node (ref "R107") (pin "1") (pinfunction "1_1") (pintype "passive"))
      (node (ref "R108") (pin "2") (pinfunction "2_2") (pintype "passive"))
      (node (ref "R14") (pin "1") (pinfunction "1_1") (pintype "passive"))
      (node (ref "R5") (pin "1") (pinfunction "1_1") (pintype "passive"))
      (node (ref "R6") (pin "1") (pinfunction "1_1") (pintype "passive"))
      (node (ref "R7") (pin "1") (pinfunction "1_1") (pintype "passive"))
      (node (ref "RJ6") (pin "1") (pinfunction "1_1") (pintype "passive"))
      (node (ref "RJ6") (pin "2") (pinfunction "2_2") (pintype "passive"))
      (node (ref "RJ8") (pin "1") (pinfunction "1_1") (pintype "passive"))
      (node (ref "RJ8") (pin "2") (pinfunction "2_2") (pintype "passive"))
      (node (ref "U3") (pin "8") (pinfunction "VCC_8") (pintype "passive"))
      (node (ref "ZD1") (pin "2") (pinfunction "K_2") (pintype "passive"))
    )
    (net (code "8") (name "/Current_IU") (class "Default")
      (node (ref "C36") (pin "1") (pinfunction "1_1") (pintype "passive"))
      (node (ref "C41") (pin "2") (pinfunction "2_2") (pintype "passive"))
      (node (ref "IC2") (pin "14") (pinfunction "PA05_14") (pintype "passive"))
      (node (ref "R11") (pin "2") (pinfunction "2_2") (pintype "passive"))
      (node (ref "R58") (pin "1") (pinfunction "1_1") (pintype "passive"))
    )
    (net (code "9") (name "/Current_IV") (class "Default")
      (node (ref "C23") (pin "1") (pinfunction "1_1") (pintype "passive"))
      (node (ref "C42") (pin "1") (pinfunction "1_1") (pintype "passive"))
      (node (ref "IC2") (pin "13") (pinfunction "PA04_13") (pintype "passive"))
      (node (ref "R60") (pin "1") (pinfunction "1_1") (pintype "passive"))
      (node (ref "R67") (pin "2") (pinfunction "2_2") (pintype "passive"))
    )
    (net (code "10") (name "/Fault") (class "Default")
      (node (ref "C44") (pin "1") (pinfunction "1_1") (pintype "passive"))
      (node (ref "IC2") (pin "39") (pinfunction "PB06_39") (pintype "passive"))
      (node (ref "R21") (pin "2") (pinfunction "2_2") (pintype "passive"))
      (node (ref "U3") (pin "14") (pinfunction "VFO_14") (pintype "passive"))
    )
    (net (code "11") (name "/HOST_RXD") (class "Default")
      (node (ref "CN4") (pin "2") (pinfunction "2_2") (pintype "passive"))
      (node (ref "R71") (pin "1") (pinfunction "1_1") (pintype "passive"))
    )
    (net (code "12") (name "/HOST_TXD") (class "Default")
      (node (ref "C61") (pin "1") (pinfunction "1_1") (pintype "passive"))
      (node (ref "CN4") (pin "3") (pinfunction "3_3") (pintype "passive"))
      (node (ref "R59") (pin "1") (pinfunction "1_1") (pintype "passive"))
    )
    (net (code "13") (name "/ISU") (class "Default")
      (node (ref "C37") (pin "2") (pinfunction "2_2") (pintype "passive"))
      (node (ref "C38") (pin "2") (pinfunction "2_2") (pintype "passive"))
      (node (ref "R76") (pin "2") (pinfunction "2_2") (pintype "passive"))
      (node (ref "R82") (pin "1") (pinfunction "1_1") (pintype "passive"))
      (node (ref "R84") (pin "1") (pinfunction "1_1") (pintype "passive"))
      (node (ref "RJ1") (pin "1") (pinfunction "1_1") (pintype "passive"))
      (node (ref "RJ1") (pin "2") (pinfunction "2_2") (pintype "passive"))
      (node (ref "U3") (pin "20") (pinfunction "NU_20") (pintype "passive"))
    )
    (net (code "14") (name "/ISV") (class "Default")
      (node (ref "C34") (pin "2") (pinfunction "2_2") (pintype "passive"))
      (node (ref "C45") (pin "1") (pinfunction "1_1") (pintype "passive"))
      (node (ref "R53") (pin "1") (pinfunction "1_1") (pintype "passive"))
      (node (ref "R78") (pin "2") (pinfunction "2_2") (pintype "passive"))
      (node (ref "R86") (pin "1") (pinfunction "1_1") (pintype "passive"))
      (node (ref "U3") (pin "19") (pinfunction "NV_19") (pintype "passive"))
    )
    (net (code "17") (name "/L") (class "Default")
      (node (ref "CN1") (pin "2") (pinfunction "2_2") (pintype "passive"))
      (node (ref "K1") (pin "4") (pinfunction "4_4") (pintype "passive"))
      (node (ref "K10") (pin "3") (pinfunction "3_3") (pintype "passive"))
      (node (ref "K2") (pin "3") (pinfunction "3_3") (pintype "passive"))
      (node (ref "K3") (pin "3") (pinfunction "3_3") (pintype "passive"))
      (node (ref "K4") (pin "3") (pinfunction "3_3") (pintype "passive"))
      (node (ref "R19") (pin "2") (pinfunction "2_2") (pintype "passive"))
      (node (ref "VR1") (pin "1") (pinfunction "1_1") (pintype "passive"))
    )
    (net (code "18") (name "/LED") (class "Default")
      (node (ref "D8") (pin "2") (pinfunction "K_2") (pintype "passive"))
      (node (ref "IC2") (pin "41") (pinfunction "PD03_41") (pintype "passive"))
    )
    (net (code "23") (name "/OPU+") (class "Default")
      (node (ref "IC2") (pin "23") (pinfunction "PB13_23") (pintype "passive"))
      (node (ref "R12") (pin "2") (pinfunction "2_2") (pintype "passive"))
      (node (ref "R54") (pin "1") (pinfunction "1_1") (pintype "passive"))
      (node (ref "R55") (pin "2") (pinfunction "2_2") (pintype "passive"))
      (node (ref "R77") (pin "1") (pinfunction "1_1") (pintype "passive"))
      (node (ref "R82") (pin "2") (pinfunction "2_2") (pintype "passive"))
      (node (ref "R84") (pin "2") (pinfunction "2_2") (pintype "passive"))
      (node (ref "U6") (pin "3") (pinfunction "1IN+_3") (pintype "passive"))
    )
    (net (code "24") (name "/OPU-") (class "Default")
      (node (ref "IC2") (pin "22") (pinfunction "PB12_22") (pintype "passive"))
      (node (ref "R15") (pin "2") (pinfunction "2_2") (pintype "passive"))
      (node (ref "R28") (pin "2") (pinfunction "2_2") (pintype "passive"))
      (node (ref "R30") (pin "2") (pinfunction "2_2") (pintype "passive"))
      (node (ref "R32") (pin "2") (pinfunction "2_2") (pintype "passive"))
      (node (ref "R81") (pin "2") (pinfunction "2_2") (pintype "passive"))
      (node (ref "R83") (pin "2") (pinfunction "2_2") (pintype "passive"))
      (node (ref "U6") (pin "2") (pinfunction "1IN-_2") (pintype "passive"))
    )
    (net (code "25") (name "/OPU_Out") (class "Default")
      (node (ref "IC2") (pin "24") (pinfunction "PB14_24") (pintype "passive"))
      (node (ref "R11") (pin "1") (pinfunction "1_1") (pintype "passive"))
      (node (ref "R15") (pin "1") (pinfunction "1_1") (pintype "passive"))
      (node (ref "R28") (pin "1") (pinfunction "1_1") (pintype "passive"))
      (node (ref "R30") (pin "1") (pinfunction "1_1") (pintype "passive"))
      (node (ref "R32") (pin "1") (pinfunction "1_1") (pintype "passive"))
      (node (ref "R58") (pin "2") (pinfunction "2_2") (pintype "passive"))
      (node (ref "U6") (pin "1") (pinfunction "1OUT_1") (pintype "passive"))
    )
    (net (code "26") (name "/OPV+") (class "Default")
      (node (ref "R16") (pin "1") (pinfunction "1_1") (pintype "passive"))
      (node (ref "R20") (pin "2") (pinfunction "2_2") (pintype "passive"))
      (node (ref "R48") (pin "1") (pinfunction "1_1") (pintype "passive"))
      (node (ref "R50") (pin "2") (pinfunction "2_2") (pintype "passive"))
      (node (ref "R53") (pin "2") (pinfunction "2_2") (pintype "passive"))
      (node (ref "R86") (pin "2") (pinfunction "2_2") (pintype "passive"))
      (node (ref "RJ3") (pin "1") (pinfunction "1_1") (pintype "passive"))
      (node (ref "U6") (pin "5") (pinfunction "2IN+_5") (pintype "passive"))
    )
    (net (code "27") (name "/OPV-") (class "Default")
      (node (ref "IC2") (pin "19") (pinfunction "PB02_19") (pintype "passive"))
      (node (ref "R18") (pin "2") (pinfunction "2_2") (pintype "passive"))
      (node (ref "R29") (pin "2") (pinfunction "2_2") (pintype "passive"))
      (node (ref "R46") (pin "2") (pinfunction "2_2") (pintype "passive"))
      (node (ref "R47") (pin "2") (pinfunction "2_2") (pintype "passive"))
      (node (ref "R52") (pin "2") (pinfunction "2_2") (pintype "passive"))
      (node (ref "R85") (pin "2") (pinfunction "2_2") (pintype "passive"))
      (node (ref "U6") (pin "6") (pinfunction "2IN-_6") (pintype "passive"))
    )
    (net (code "28") (name "/OPV_Out") (class "Default")
      (node (ref "IC2") (pin "21") (pinfunction "PB11_21") (pintype "passive"))
      (node (ref "R18") (pin "1") (pinfunction "1_1") (pintype "passive"))
      (node (ref "R29") (pin "1") (pinfunction "1_1") (pintype "passive"))
      (node (ref "R46") (pin "1") (pinfunction "1_1") (pintype "passive"))
      (node (ref "R47") (pin "1") (pinfunction "1_1") (pintype "passive"))
      (node (ref "R60") (pin "2") (pinfunction "2_2") (pintype "passive"))
      (node (ref "R67") (pin "1") (pinfunction "1_1") (pintype "passive"))
      (node (ref "U6") (pin "7") (pinfunction "2OUT_7") (pintype "passive"))
    )
    (net (code "32") (name "/Relay") (class "Default")
      (node (ref "IC2") (pin "32") (pinfunction "PD06_32") (pintype "passive"))
      (node (ref "R23") (pin "1") (pinfunction "1_1") (pintype "passive"))
    )
    (net (code "33") (name "/SCL0") (class "Default")
      (node (ref "IC2") (pin "42") (pinfunction "PB08_42") (pintype "passive"))
      (node (ref "R115") (pin "2") (pinfunction "2_2") (pintype "passive"))
      (node (ref "R116") (pin "2") (pinfunction "2_2") (pintype "passive"))
    )
    (net (code "34") (name "/SDA0") (class "Default")
      (node (ref "IC2") (pin "40") (pinfunction "PB07_40") (pintype "passive"))
      (node (ref "R110") (pin "2") (pinfunction "2_2") (pintype "passive"))
      (node (ref "R114") (pin "2") (pinfunction "2_2") (pintype "passive"))
    )
    (net (code "35") (name "/SWCLK") (class "Default")
      (node (ref "IC2") (pin "34") (pinfunction "PA14/SWCLK_34") (pintype "passive"))
      (node (ref "R9") (pin "2") (pinfunction "2_2") (pintype "passive"))
    )
    (net (code "36") (name "/SWDIO") (class "Default")
      (node (ref "IC2") (pin "31") (pinfunction "PA13/SWDIO_31") (pintype "passive"))
      (node (ref "R8") (pin "2") (pinfunction "2_2") (pintype "passive"))
    )
    (net (code "37") (name "/TEMP") (class "Default")
      (node (ref "C30") (pin "1") (pinfunction "1_1") (pintype "passive"))
      (node (ref "IC2") (pin "10") (pinfunction "PA01_10") (pintype "passive"))
      (node (ref "R3") (pin "2") (pinfunction "2_2") (pintype "passive"))
    )
    (net (code "39") (name "/U") (class "Default")
      (node (ref "C12") (pin "1") (pinfunction "1_1") (pintype "passive"))
      (node (ref "C8") (pin "1") (pinfunction "1_1") (pintype "passive"))
      (node (ref "CN6") (pin "1") (pinfunction "1_1") (pintype "passive"))
      (node (ref "J13") (pin "1") (pinfunction "1_1") (pintype "passive"))
      (node (ref "J13") (pin "2") (pinfunction "2_2") (pintype "passive"))
      (node (ref "U3") (pin "23") (pinfunction "U_23") (pintype "passive"))
    )
    (net (code "40") (name "/U1A_RX") (class "Default")
      (node (ref "C60") (pin "1") (pinfunction "1_1") (pintype "passive"))
      (node (ref "IC2") (pin "12") (pinfunction "PA03_12") (pintype "passive"))
      (node (ref "R75") (pin "1") (pinfunction "1_1") (pintype "passive"))
      (node (ref "U5") (pin "4") (pinfunction "C_4") (pintype "passive"))
    )
    (net (code "41") (name "/U1A_TX") (class "Default")
      (node (ref "IC2") (pin "11") (pinfunction "PA02_11") (pintype "passive"))
      (node (ref "R68") (pin "2") (pinfunction "2_2") (pintype "passive"))
    )
    (net (code "42") (name "/UH") (class "Default")
      (node (ref "IC2") (pin "28") (pinfunction "PA10_28") (pintype "passive"))
      (node (ref "U3") (pin "5") (pinfunction "UP_5") (pintype "passive"))
    )
    (net (code "43") (name "/UL") (class "Default")
      (node (ref "IC2") (pin "18") (pinfunction "PB01_18") (pintype "passive"))
      (node (ref "U3") (pin "10") (pinfunction "UN_10") (pintype "passive"))
    )
    (net (code "44") (name "/V") (class "Default")
      (node (ref "C1") (pin "1") (pinfunction "1_1") (pintype "passive"))
      (node (ref "C2") (pin "2") (pinfunction "2_2") (pintype "passive"))
      (node (ref "CN6") (pin "2") (pinfunction "2_2") (pintype "passive"))
      (node (ref "J14") (pin "1") (pinfunction "1_1") (pintype "passive"))
      (node (ref "J14") (pin "2") (pinfunction "2_2") (pintype "passive"))
      (node (ref "U3") (pin "22") (pinfunction "V_22") (pintype "passive"))
    )
    (net (code "46") (name "/VDC") (class "Default")
      (node (ref "C50") (pin "1") (pinfunction "1_1") (pintype "passive"))
      (node (ref "C51") (pin "1") (pinfunction "1_1") (pintype "passive"))
      (node (ref "IC2") (pin "9") (pinfunction "PA00_9") (pintype "passive"))
      (node (ref "R56") (pin "1") (pinfunction "1_1") (pintype "passive"))
    )
    (net (code "47") (name "/VH") (class "Default")
      (node (ref "IC2") (pin "27") (pinfunction "PA09_27") (pintype "passive"))
      (node (ref "U3") (pin "6") (pinfunction "VP_6") (pintype "passive"))
    )
    (net (code "48") (name "/VL") (class "Default")
      (node (ref "IC2") (pin "17") (pinfunction "PB00_17") (pintype "passive"))
      (node (ref "U3") (pin "11") (pinfunction "VN_11") (pintype "passive"))
    )
    (net (code "49") (name "/W") (class "Default")
      (node (ref "C3") (pin "2") (pinfunction "2_2") (pintype "passive"))
      (node (ref "C4") (pin "1") (pinfunction "1_1") (pintype "passive"))
      (node (ref "CN6") (pin "3") (pinfunction "3_3") (pintype "passive"))
      (node (ref "CN6") (pin "4") (pinfunction "4_4") (pintype "passive"))
      (node (ref "J15") (pin "1") (pinfunction "1_1") (pintype "passive"))
      (node (ref "J15") (pin "2") (pinfunction "2_2") (pintype "passive"))
      (node (ref "U3") (pin "21") (pinfunction "W_21") (pintype "passive"))
    )
    (net (code "50") (name "/WH") (class "Default")
      (node (ref "RJ5") (pin "1") (pinfunction "1_1") (pintype "passive"))
      (node (ref "U3") (pin "7") (pinfunction "WP_7") (pintype "passive"))
    )
    (net (code "51") (name "/WL") (class "Default")
      (node (ref "IC2") (pin "16") (pinfunction "PA07_16") (pintype "passive"))
      (node (ref "U3") (pin "12") (pinfunction "WN_12") (pintype "passive"))
    )
    (net (code "55") (name "/XTHI") (class "Default")
      (node (ref "C66") (pin "1") (pinfunction "1_1") (pintype "passive"))
      (node (ref "IC2") (pin "4") (pinfunction "XTHI/PD00_4") (pintype "passive"))
      (node (ref "Y1") (pin "2") (pinfunction "OSC2_2") (pintype "passive"))
    )
    (net (code "56") (name "/XTHO") (class "Default")
      (node (ref "C65") (pin "1") (pinfunction "1_1") (pintype "passive"))
      (node (ref "IC2") (pin "5") (pinfunction "XTHO/PD01_5") (pintype "passive"))
      (node (ref "Y1") (pin "1") (pinfunction "OSC1_1") (pintype "passive"))
    )
    (net (code "57") (name "/md") (class "Default")
      (node (ref "CN7") (pin "1") (pinfunction "1_1") (pintype "passive"))
      (node (ref "R61") (pin "2") (pinfunction "2_2") (pintype "passive"))
      (node (ref "R79") (pin "2") (pinfunction "2_2") (pintype "passive"))
    )
    (net (code "58") (name "/ms") (class "Default")
      (node (ref "C62") (pin "1") (pinfunction "1_1") (pintype "passive"))
      (node (ref "C63") (pin "1") (pinfunction "1_1") (pintype "passive"))
      (node (ref "IC2") (pin "15") (pinfunction "PA06_15") (pintype "passive"))
      (node (ref "R61") (pin "1") (pinfunction "1_1") (pintype "passive"))
    )
    (net (code "62") (name "/排水") (class "Default")
      (node (ref "D502") (pin "1") (pinfunction "1_1") (pintype "passive"))
      (node (ref "K3") (pin "1") (pinfunction "1_1") (pintype "passive"))
      (node (ref "Q4") (pin "3") (pinfunction "C_3") (pintype "passive"))
    )
    (net (code "63") (name "/排水R") (class "Default")
      (node (ref "IC2") (pin "36") (pinfunction "PB03_36") (pintype "passive"))
      (node (ref "R2") (pin "1") (pinfunction "1_1") (pintype "passive"))
    )
    (net (code "67") (name "/牵引器") (class "Default")
      (node (ref "D501") (pin "1") (pinfunction "1_1") (pintype "passive"))
      (node (ref "K10") (pin "1") (pinfunction "1_1") (pintype "passive"))
      (node (ref "Q3") (pin "3") (pinfunction "C_3") (pintype "passive"))
    )
    (net (code "68") (name "/牵引器R") (class "Default")
      (node (ref "IC2") (pin "33") (pinfunction "PD07_33") (pintype "passive"))
      (node (ref "R1") (pin "1") (pinfunction "1_1") (pintype "passive"))
    )
    (net (code "69") (name "/进水1") (class "Default")
      (node (ref "D503") (pin "1") (pinfunction "1_1") (pintype "passive"))
      (node (ref "K4") (pin "1") (pinfunction "1_1") (pintype "passive"))
      (node (ref "Q5") (pin "3") (pinfunction "C_3") (pintype "passive"))
    )
    (net (code "70") (name "/进水1R") (class "Default")
      (node (ref "IC2") (pin "37") (pinfunction "PB04_37") (pintype "passive"))
      (node (ref "R37") (pin "1") (pinfunction "1_1") (pintype "passive"))
    )
    (net (code "71") (name "/进水2") (class "Default")
      (node (ref "D504") (pin "1") (pinfunction "1_1") (pintype "passive"))
      (node (ref "K1") (pin "1") (pinfunction "1_1") (pintype "passive"))
      (node (ref "Q6") (pin "3") (pinfunction "C_3") (pintype "passive"))
    )
    (net (code "72") (name "/进水2R") (class "Default")
      (node (ref "IC2") (pin "38") (pinfunction "PB05_38") (pintype "passive"))
      (node (ref "R33") (pin "1") (pinfunction "1_1") (pintype "passive"))
    )
    (net (code "74") (name "18V") (class "Default")
      (node (ref "C104") (pin "1") (pinfunction "1_1") (pintype "passive"))
      (node (ref "C32") (pin "1") (pinfunction "1_1") (pintype "passive"))
      (node (ref "D3") (pin "2") (pinfunction "K_2") (pintype "passive"))
      (node (ref "R104") (pin "1") (pinfunction "1_1") (pintype "passive"))
      (node (ref "U101") (pin "6") (pinfunction "VCC_6") (pintype "passive"))
    )
    (net (code "75") (name "AGND") (class "Default")
      (node (ref "C23") (pin "2") (pinfunction "2_2") (pintype "passive"))
      (node (ref "C24") (pin "1") (pinfunction "1_1") (pintype "passive"))
      (node (ref "C36") (pin "2") (pinfunction "2_2") (pintype "passive"))
      (node (ref "C39") (pin "2") (pinfunction "2_2") (pintype "passive"))
      (node (ref "C40") (pin "2") (pinfunction "2_2") (pintype "passive"))
      (node (ref "C41") (pin "1") (pinfunction "1_1") (pintype "passive"))
      (node (ref "C42") (pin "2") (pinfunction "2_2") (pintype "passive"))
      (node (ref "C54") (pin "1") (pinfunction "1_1") (pintype "passive"))
      (node (ref "C62") (pin "2") (pinfunction "2_2") (pintype "passive"))
      (node (ref "C63") (pin "2") (pinfunction "2_2") (pintype "passive"))
      (node (ref "IC2") (pin "7") (pinfunction "AVSS_7") (pintype "passive"))
      (node (ref "J16") (pin "1") (pinfunction "1_1") (pintype "passive"))
      (node (ref "J16") (pin "2") (pinfunction "2_2") (pintype "passive"))
      (node (ref "R12") (pin "1") (pinfunction "1_1") (pintype "passive"))
      (node (ref "R20") (pin "1") (pinfunction "1_1") (pintype "passive"))
      (node (ref "R391") (pin "2") (pinfunction "2_2") (pintype "passive"))
      (node (ref "R50") (pin "1") (pinfunction "1_1") (pintype "passive"))
      (node (ref "R55") (pin "1") (pinfunction "1_1") (pintype "passive"))
      (node (ref "R79") (pin "1") (pinfunction "1_1") (pintype "passive"))
      (node (ref "RJ4") (pin "1") (pinfunction "1_1") (pintype "passive"))
      (node (ref "RJ4") (pin "2") (pinfunction "2_2") (pintype "passive"))
      (node (ref "U6") (pin "10") (pinfunction "3IN+_10") (pintype "passive"))
      (node (ref "U6") (pin "11") (pinfunction "GND_11") (pintype "passive"))
      (node (ref "U6") (pin "12") (pinfunction "4IN+_12") (pintype "passive"))
    )
    (net (code "77") (name "EARTH") (class "Default")
      (node (ref "CN2") (pin "1") (pinfunction "1_1") (pintype "passive"))
      (node (ref "R26") (pin "1") (pinfunction "1_1") (pintype "passive"))
      (node (ref "R27") (pin "1") (pinfunction "1_1") (pintype "passive"))
    )
    (net (code "78") (name "GND") (class "Default")
      (node (ref "BD1") (pin "1") (pinfunction "V-_1") (pintype "passive"))
      (node (ref "C104") (pin "2") (pinfunction "2_2") (pintype "passive"))
      (node (ref "C106") (pin "2") (pinfunction "2_2") (pintype "passive"))
      (node (ref "C108") (pin "2") (pinfunction "2_2") (pintype "passive"))
      (node (ref "C109") (pin "2") (pinfunction "2_2") (pintype "passive"))
      (node (ref "C11") (pin "2") (pinfunction "2_2") (pintype "passive"))
      (node (ref "C13") (pin "1") (pinfunction "1_1") (pintype "passive"))
      (node (ref "C14") (pin "2") (pinfunction "2_2") (pintype "passive"))
      (node (ref "C15") (pin "2") (pinfunction "2_2") (pintype "passive"))
      (node (ref "C16") (pin "2") (pinfunction "2_2") (pintype "passive"))
      (node (ref "C166") (pin "2") (pinfunction "2_2") (pintype "passive"))
      (node (ref "C17") (pin "2") (pinfunction "2_2") (pintype "passive"))
      (node (ref "C18") (pin "1") (pinfunction "1_1") (pintype "passive"))
      (node (ref "C19") (pin "2") (pinfunction "2_2") (pintype "passive"))
      (node (ref "C20") (pin "2") (pinfunction "2_2") (pintype "passive"))
      (node (ref "C21") (pin "2") (pinfunction "2_2") (pintype "passive"))
      (node (ref "C241") (pin "1") (pinfunction "1_1") (pintype "passive"))
      (node (ref "C27") (pin "2") (pinfunction "2_2") (pintype "passive"))
      (node (ref "C30") (pin "2") (pinfunction "2_2") (pintype "passive"))
      (node (ref "C32") (pin "2") (pinfunction "2_2") (pintype "passive"))
      (node (ref "C33") (pin "2") (pinfunction "2_2") (pintype "passive"))
      (node (ref "C34") (pin "1") (pinfunction "1_1") (pintype "passive"))
      (node (ref "C35") (pin "1") (pinfunction "1_1") (pintype "passive"))
      (node (ref "C37") (pin "1") (pinfunction "1_1") (pintype "passive"))
      (node (ref "C38") (pin "1") (pinfunction "1_1") (pintype "passive"))
      (node (ref "C44") (pin "2") (pinfunction "2_2") (pintype "passive"))
      (node (ref "C45") (pin "2") (pinfunction "2_2") (pintype "passive"))
      (node (ref "C5") (pin "2") (pinfunction "2_2") (pintype "passive"))
      (node (ref "C50") (pin "2") (pinfunction "2_2") (pintype "passive"))
      (node (ref "C51") (pin "2") (pinfunction "2_2") (pintype "passive"))
      (node (ref "C56") (pin "1") (pinfunction "1_1") (pintype "passive"))
      (node (ref "C57") (pin "2") (pinfunction "2_2") (pintype "passive"))
      (node (ref "C60") (pin "2") (pinfunction "2_2") (pintype "passive"))
      (node (ref "C64") (pin "2") (pinfunction "2_2") (pintype "passive"))
      (node (ref "C65") (pin "2") (pinfunction "2_2") (pintype "passive"))
      (node (ref "C66") (pin "2") (pinfunction "2_2") (pintype "passive"))
      (node (ref "CN10") (pin "4") (pinfunction "4_4") (pintype "passive"))
      (node (ref "CN8") (pin "2") (pinfunction "2_2") (pintype "passive"))
      (node (ref "D105") (pin "1") (pinfunction "A_1") (pintype "passive"))
      (node (ref "IC2") (pin "43") (pinfunction "DVSS_43") (pintype "passive"))
      (node (ref "J12") (pin "1") (pinfunction "1_1") (pintype "passive"))
      (node (ref "J12") (pin "2") (pinfunction "2_2") (pintype "passive"))
      (node (ref "J19") (pin "1") (pinfunction "1_1") (pintype "passive"))
      (node (ref "J19") (pin "2") (pinfunction "2_2") (pintype "passive"))
      (node (ref "J20") (pin "1") (pinfunction "1_1") (pintype "passive"))
      (node (ref "J20") (pin "2") (pinfunction "2_2") (pintype "passive"))
      (node (ref "J26") (pin "1") (pinfunction "1_1") (pintype "passive"))
      (node (ref "J26") (pin "2") (pinfunction "2_2") (pintype "passive"))
      (node (ref "J28") (pin "1") (pinfunction "1_1") (pintype "passive"))
      (node (ref "J28") (pin "2") (pinfunction "2_2") (pintype "passive"))
      (node (ref "J31") (pin "1") (pinfunction "1_1") (pintype "passive"))
      (node (ref "J31") (pin "2") (pinfunction "2_2") (pintype "passive"))
      (node (ref "J32") (pin "1") (pinfunction "1_1") (pintype "passive"))
      (node (ref "J32") (pin "2") (pinfunction "2_2") (pintype "passive"))
      (node (ref "Q1") (pin "2") (pinfunction "E_2") (pintype "passive"))
      (node (ref "Q3") (pin "2") (pinfunction "E_2") (pintype "passive"))
      (node (ref "Q4") (pin "2") (pinfunction "E_2") (pintype "passive"))
      (node (ref "Q5") (pin "2") (pinfunction "E_2") (pintype "passive"))
      (node (ref "Q6") (pin "2") (pinfunction "E_2") (pintype "passive"))
      (node (ref "R10") (pin "1") (pinfunction "1_1") (pintype "passive"))
      (node (ref "R101") (pin "2") (pinfunction "2_2") (pintype "passive"))
      (node (ref "R105") (pin "2") (pinfunction "2_2") (pintype "passive"))
      (node (ref "R13") (pin "1") (pinfunction "1_1") (pintype "passive"))
      (node (ref "R131") (pin "1") (pinfunction "1_1") (pintype "passive"))
      (node (ref "R31") (pin "1") (pinfunction "1_1") (pintype "passive"))
      (node (ref "R310") (pin "2") (pinfunction "2_2") (pintype "passive"))
      (node (ref "R34") (pin "1") (pinfunction "1_1") (pintype "passive"))
      (node (ref "R391") (pin "1") (pinfunction "1_1") (pintype "passive"))
      (node (ref "R43") (pin "1") (pinfunction "1_1") (pintype "passive"))
      (node (ref "R52") (pin "1") (pinfunction "1_1") (pintype "passive"))
      (node (ref "R63") (pin "1") (pinfunction "1_1") (pintype "passive"))
      (node (ref "R69") (pin "1") (pinfunction "1_1") (pintype "passive"))
      (node (ref "R76") (pin "1") (pinfunction "1_1") (pintype "passive"))
      (node (ref "R78") (pin "1") (pinfunction "1_1") (pintype "passive"))
      (node (ref "R81") (pin "1") (pinfunction "1_1") (pintype "passive"))
      (node (ref "R83") (pin "1") (pinfunction "1_1") (pintype "passive"))
      (node (ref "R85") (pin "1") (pinfunction "1_1") (pintype "passive"))
      (node (ref "R87") (pin "1") (pinfunction "1_1") (pintype "passive"))
      (node (ref "R87") (pin "2") (pinfunction "2_2") (pintype "passive"))
      (node (ref "RJ11") (pin "1") (pinfunction "1_1") (pintype "passive"))
      (node (ref "RJ11") (pin "2") (pinfunction "2_2") (pintype "passive"))
      (node (ref "RJ2") (pin "1") (pinfunction "1_1") (pintype "passive"))
      (node (ref "RJ2") (pin "2") (pinfunction "2_2") (pintype "passive"))
      (node (ref "RJ7") (pin "1") (pinfunction "1_1") (pintype "passive"))
      (node (ref "RJ7") (pin "2") (pinfunction "2_2") (pintype "passive"))
      (node (ref "T1") (pin "5") (pinfunction "5_5") (pintype "passive"))
      (node (ref "U1") (pin "2") (pinfunction "(2)GND_2") (pintype "passive"))
      (node (ref "U100") (pin "5") (pinfunction "S_5") (pintype "passive"))
      (node (ref "U100") (pin "6") (pinfunction "S_6") (pintype "passive"))
      (node (ref "U100") (pin "7") (pinfunction "S_7") (pintype "passive"))
      (node (ref "U100") (pin "8") (pinfunction "S_8") (pintype "passive"))
      (node (ref "U101") (pin "4") (pinfunction "GND_4") (pintype "power_in"))
      (node (ref "U2") (pin "3") (pinfunction "E_3") (pintype "passive"))
      (node (ref "U3") (pin "16") (pinfunction "COM_16") (pintype "passive"))
      (node (ref "U3") (pin "18") (pinfunction "NW_18") (pintype "passive"))
      (node (ref "U3") (pin "9") (pinfunction "COM_9") (pintype "passive"))
      (node (ref "U4") (pin "2") (pinfunction "K_2") (pintype "passive"))
      (node (ref "U5") (pin "3") (pinfunction "E_3") (pintype "passive"))
      (node (ref "ZD1") (pin "1") (pinfunction "A_1") (pintype "passive"))
    )
    (net (code "80") (name "N") (class "Default")
      (node (ref "C6") (pin "1") (pinfunction "1_1") (pintype "passive"))
      (node (ref "CN1") (pin "1") (pinfunction "1_1") (pintype "passive"))
      (node (ref "CN14") (pin "1") (pinfunction "1_1") (pintype "passive"))
      (node (ref "CN5") (pin "1") (pinfunction "1_1") (pintype "passive"))
      (node (ref "L1") (pin "3") (pinfunction "3_3") (pintype "passive"))
      (node (ref "R39") (pin "1") (pinfunction "1_1") (pintype "passive"))
      (node (ref "VR1") (pin "2") (pinfunction "2_2") (pintype "passive"))
    )
    (net (code "81") (name "Net-(BD1-AC-Pad2)") (class "Default")
      (node (ref "BD1") (pin "2") (pinfunction "AC_2") (pintype "passive"))
      (node (ref "L1") (pin "4") (pinfunction "4_4") (pintype "passive"))
    )
    (net (code "82") (name "Net-(BD1-AC-Pad3)") (class "Default")
      (node (ref "BD1") (pin "3") (pinfunction "AC_3") (pintype "passive"))
      (node (ref "L1") (pin "1") (pinfunction "1_1") (pintype "passive"))
    )
    (net (code "83") (name "Net-(C6-Pad2)") (class "Default")
      (node (ref "C6") (pin "2") (pinfunction "2_2") (pintype "passive"))
      (node (ref "K2") (pin "4") (pinfunction "4_4") (pintype "passive"))
      (node (ref "L1") (pin "2") (pinfunction "2_2") (pintype "passive"))
      (node (ref "R19") (pin "1") (pinfunction "1_1") (pintype "passive"))
      (node (ref "R36") (pin "2") (pinfunction "2_2") (pintype "passive"))
    )
    (net (code "84") (name "Net-(C35-Pad2)") (class "Default")
      (node (ref "C35") (pin "2") (pinfunction "2_2") (pintype "passive"))
      (node (ref "R26") (pin "2") (pinfunction "2_2") (pintype "passive"))
      (node (ref "R27") (pin "2") (pinfunction "2_2") (pintype "passive"))
    )
    (net (code "85") (name "Net-(C166-Pad1)") (class "Default")
      (node (ref "C166") (pin "1") (pinfunction "1_1") (pintype "passive"))
      (node (ref "U100") (pin "2") (pintype "passive"))
    )
    (net (code "86") (name "Net-(CN3-Pad1)") (class "Default")
      (node (ref "CN3") (pin "1") (pinfunction "1_1") (pintype "passive"))
      (node (ref "K4") (pin "4") (pinfunction "4_4") (pintype "passive"))
    )
    (net (code "87") (name "Net-(CN5-Pad2)") (class "Default")
      (node (ref "CN5") (pin "2") (pinfunction "2_2") (pintype "passive"))
      (node (ref "K10") (pin "4") (pinfunction "4_4") (pintype "passive"))
    )
    (net (code "88") (name "Net-(CN8-Pad3)") (class "Default")
      (node (ref "CN8") (pin "3") (pinfunction "3_3") (pintype "passive"))
      (node (ref "R8") (pin "1") (pinfunction "1_1") (pintype "passive"))
    )
    (net (code "89") (name "Net-(CN8-Pad4)") (class "Default")
      (node (ref "CN8") (pin "4") (pinfunction "4_4") (pintype "passive"))
      (node (ref "R9") (pin "1") (pinfunction "1_1") (pintype "passive"))
    )
    (net (code "90") (name "Net-(CN9-Pad1)") (class "Default")
      (node (ref "CN9") (pin "1") (pinfunction "1_1") (pintype "passive"))
      (node (ref "K1") (pin "3") (pinfunction "3_3") (pintype "passive"))
    )
    (net (code "91") (name "Net-(CN10-Pad2)") (class "Default")
      (node (ref "CN10") (pin "2") (pinfunction "2_2") (pintype "passive"))
      (node (ref "R114") (pin "1") (pinfunction "1_1") (pintype "passive"))
    )
    (net (code "92") (name "Net-(CN10-Pad3)") (class "Default")
      (node (ref "CN10") (pin "3") (pinfunction "3_3") (pintype "passive"))
      (node (ref "R115") (pin "1") (pinfunction "1_1") (pintype "passive"))
    )
    (net (code "93") (name "Net-(CN14-Pad2)") (class "Default")
      (node (ref "CN14") (pin "2") (pinfunction "2_2") (pintype "passive"))
      (node (ref "K3") (pin "4") (pinfunction "4_4") (pintype "passive"))
    )
    (net (code "94") (name "Net-(D3-A)") (class "Default")
      (node (ref "D3") (pin "1") (pinfunction "A_1") (pintype "passive"))
      (node (ref "T1") (pin "7") (pinfunction "7_7") (pintype "passive"))
    )
    (net (code "95") (name "Net-(D4-Pad2)") (class "Default")
      (node (ref "D4") (pin "2") (pinfunction "2_2") (pintype "passive"))
      (node (ref "K2") (pin "2") (pinfunction "2_2") (pintype "passive"))
      (node (ref "R107") (pin "2") (pinfunction "2_2") (pintype "passive"))
    )
    (net (code "96") (name "Net-(D5-A)") (class "Default")
      (node (ref "D5") (pin "1") (pinfunction "A_1") (pintype "passive"))
      (node (ref "T1") (pin "6") (pinfunction "6_6") (pintype "passive"))
    )
    (net (code "97") (name "Net-(D7-Pad1)") (class "Default")
      (node (ref "D7") (pin "1") (pinfunction "1_1") (pintype "passive"))
      (node (ref "R56") (pin "2") (pinfunction "2_2") (pintype "passive"))
      (node (ref "R57") (pin "1") (pinfunction "1_1") (pintype "passive"))
      (node (ref "R63") (pin "2") (pinfunction "2_2") (pintype "passive"))
    )
    (net (code "98") (name "Net-(D8-A)") (class "Default")
      (node (ref "D8") (pin "1") (pinfunction "A_1") (pintype "passive"))
      (node (ref "R4") (pin "1") (pinfunction "1_1") (pintype "passive"))
    )
    (net (code "99") (name "Net-(D105-K)") (class "Default")
      (node (ref "D105") (pin "2") (pinfunction "K_2") (pintype "passive"))
      (node (ref "L102") (pin "1") (pinfunction "1_1") (pintype "passive"))
      (node (ref "U101") (pin "2") (pinfunction "S.E._2") (pintype "passive"))
    )
    (net (code "100") (name "Net-(D162-A)") (class "Default")
      (node (ref "D162") (pin "1") (pinfunction "A_1") (pintype "passive"))
      (node (ref "T1") (pin "3") (pinfunction "3_3") (pintype "passive"))
      (node (ref "U100") (pin "4") (pinfunction "D_4") (pintype "passive"))
    )
    (net (code "101") (name "Net-(D162-K)") (class "Default")
      (node (ref "D162") (pin "2") (pinfunction "K_2") (pintype "passive"))
      (node (ref "DZ66") (pin "2") (pinfunction "K_2") (pintype "passive"))
    )
    (net (code "102") (name "Net-(D164-A)") (class "Default")
      (node (ref "D164") (pin "1") (pinfunction "A_1") (pintype "passive"))
      (node (ref "T1") (pin "10") (pinfunction "10_10") (pintype "passive"))
    )
    (net (code "103") (name "Net-(D501-Pad2)") (class "Default")
      (node (ref "D501") (pin "2") (pinfunction "2_2") (pintype "passive"))
      (node (ref "K10") (pin "2") (pinfunction "2_2") (pintype "passive"))
      (node (ref "R5") (pin "2") (pinfunction "2_2") (pintype "passive"))
    )
    (net (code "104") (name "Net-(D502-Pad2)") (class "Default")
      (node (ref "D502") (pin "2") (pinfunction "2_2") (pintype "passive"))
      (node (ref "K3") (pin "2") (pinfunction "2_2") (pintype "passive"))
      (node (ref "R6") (pin "2") (pinfunction "2_2") (pintype "passive"))
    )
    (net (code "105") (name "Net-(D503-Pad2)") (class "Default")
      (node (ref "D503") (pin "2") (pinfunction "2_2") (pintype "passive"))
      (node (ref "K4") (pin "2") (pinfunction "2_2") (pintype "passive"))
      (node (ref "R7") (pin "2") (pinfunction "2_2") (pintype "passive"))
    )
    (net (code "106") (name "Net-(D504-Pad2)") (class "Default")
      (node (ref "D504") (pin "2") (pinfunction "2_2") (pintype "passive"))
      (node (ref "K1") (pin "2") (pinfunction "2_2") (pintype "passive"))
      (node (ref "R14") (pin "2") (pinfunction "2_2") (pintype "passive"))
    )
    (net (code "107") (name "Net-(DZ21-A)") (class "Default")
      (node (ref "DZ21") (pin "1") (pinfunction "A_1") (pintype "passive"))
      (node (ref "R92") (pin "2") (pinfunction "2_2") (pintype "passive"))
      (node (ref "U2") (pin "1") (pinfunction "A_1") (pintype "passive"))
    )
    (net (code "108") (name "Net-(DZ21-K)") (class "Default")
      (node (ref "DZ21") (pin "2") (pinfunction "K_2") (pintype "passive"))
      (node (ref "R17") (pin "1") (pinfunction "1_1") (pintype "passive"))
    )
    (net (code "109") (name "Net-(IC2-PA08)") (class "Default")
      (node (ref "IC2") (pin "26") (pinfunction "PA08_26") (pintype "passive"))
      (node (ref "RJ5") (pin "2") (pinfunction "2_2") (pintype "passive"))
    )
    (net (code "110") (name "Net-(IC2-PB10)") (class "Default")
      (node (ref "IC2") (pin "20") (pinfunction "PB10_20") (pintype "passive"))
      (node (ref "RJ3") (pin "2") (pinfunction "2_2") (pintype "passive"))
    )
    (net (code "111") (name "Net-(IC2-RESETB)") (class "Default")
      (node (ref "C64") (pin "1") (pinfunction "1_1") (pintype "passive"))
      (node (ref "IC2") (pin "6") (pinfunction "RESETB_6") (pintype "passive"))
      (node (ref "R51") (pin "2") (pinfunction "2_2") (pintype "passive"))
    )
    (net (code "112") (name "Net-(IC2-VCAP)") (class "Default")
      (node (ref "C18") (pin "2") (pinfunction "2_2") (pintype "passive"))
      (node (ref "C20") (pin "1") (pinfunction "1_1") (pintype "passive"))
      (node (ref "IC2") (pin "1") (pinfunction "VCAP_1") (pintype "passive"))
    )
    (net (code "113") (name "Net-(Q1-B)") (class "Default")
      (node (ref "Q1") (pin "1") (pinfunction "B_1") (pintype "passive"))
      (node (ref "R23") (pin "2") (pinfunction "2_2") (pintype "passive"))
      (node (ref "R31") (pin "2") (pinfunction "2_2") (pintype "passive"))
    )
    (net (code "114") (name "Net-(Q1-C)") (class "Default")
      (node (ref "D4") (pin "1") (pinfunction "1_1") (pintype "passive"))
      (node (ref "K2") (pin "1") (pinfunction "1_1") (pintype "passive"))
      (node (ref "Q1") (pin "3") (pinfunction "C_3") (pintype "passive"))
    )
    (net (code "115") (name "Net-(Q2-B)") (class "Default")
      (node (ref "Q2") (pin "1") (pinfunction "B_1") (pintype "passive"))
      (node (ref "R68") (pin "1") (pinfunction "1_1") (pintype "passive"))
      (node (ref "R70") (pin "1") (pinfunction "1_1") (pintype "passive"))
    )
    (net (code "116") (name "Net-(Q2-C)") (class "Default")
      (node (ref "Q2") (pin "3") (pinfunction "C_3") (pintype "passive"))
      (node (ref "R73") (pin "1") (pinfunction "1_1") (pintype "passive"))
    )
    (net (code "117") (name "Net-(Q3-B)") (class "Default")
      (node (ref "Q3") (pin "1") (pinfunction "B_1") (pintype "passive"))
      (node (ref "R1") (pin "2") (pinfunction "2_2") (pintype "passive"))
      (node (ref "R10") (pin "2") (pinfunction "2_2") (pintype "passive"))
    )
    (net (code "118") (name "Net-(Q4-B)") (class "Default")
      (node (ref "Q4") (pin "1") (pinfunction "B_1") (pintype "passive"))
      (node (ref "R13") (pin "2") (pinfunction "2_2") (pintype "passive"))
      (node (ref "R2") (pin "2") (pinfunction "2_2") (pintype "passive"))
    )
    (net (code "119") (name "Net-(Q5-B)") (class "Default")
      (node (ref "Q5") (pin "1") (pinfunction "B_1") (pintype "passive"))
      (node (ref "R37") (pin "2") (pinfunction "2_2") (pintype "passive"))
      (node (ref "R43") (pin "2") (pinfunction "2_2") (pintype "passive"))
    )
    (net (code "120") (name "Net-(Q6-B)") (class "Default")
      (node (ref "J33") (pin "1") (pinfunction "1_1") (pintype "passive"))
      (node (ref "J33") (pin "2") (pinfunction "2_2") (pintype "passive"))
      (node (ref "Q6") (pin "1") (pinfunction "B_1") (pintype "passive"))
      (node (ref "R33") (pin "2") (pinfunction "2_2") (pintype "passive"))
      (node (ref "R34") (pin "2") (pinfunction "2_2") (pintype "passive"))
      (node (ref "RJ12") (pin "1") (pinfunction "1_1") (pintype "passive"))
      (node (ref "RJ12") (pin "2") (pinfunction "2_2") (pintype "passive"))
    )
    (net (code "121") (name "Net-(R36-Pad1)") (class "Default")
      (node (ref "R36") (pin "1") (pinfunction "1_1") (pintype "passive"))
      (node (ref "R44") (pin "2") (pinfunction "2_2") (pintype "passive"))
    )
    (net (code "122") (name "Net-(R39-Pad2)") (class "Default")
      (node (ref "R39") (pin "2") (pinfunction "2_2") (pintype "passive"))
      (node (ref "R44") (pin "1") (pinfunction "1_1") (pintype "passive"))
    )
    (net (code "123") (name "Net-(R49-Pad1)") (class "Default")
      (node (ref "R49") (pin "1") (pinfunction "1_1") (pintype "passive"))
      (node (ref "R57") (pin "2") (pinfunction "2_2") (pintype "passive"))
    )
    (net (code "124") (name "Net-(R59-Pad2)") (class "Default")
      (node (ref "R59") (pin "2") (pinfunction "2_2") (pintype "passive"))
      (node (ref "R64") (pin "1") (pinfunction "1_1") (pintype "passive"))
    )
    (net (code "125") (name "Net-(R71-Pad2)") (class "Default")
      (node (ref "R71") (pin "2") (pinfunction "2_2") (pintype "passive"))
      (node (ref "R72") (pin "1") (pinfunction "1_1") (pintype "passive"))
    )
    (net (code "126") (name "Net-(R106-Pad1)") (class "Default")
      (node (ref "R106") (pin "1") (pinfunction "1_1") (pintype "passive"))
      (node (ref "R108") (pin "1") (pinfunction "1_1") (pintype "passive"))
    )
    (net (code "127") (name "Net-(R130-Pad1)") (class "Default")
      (node (ref "R130") (pin "1") (pinfunction "1_1") (pintype "passive"))
      (node (ref "R131") (pin "2") (pinfunction "2_2") (pintype "passive"))
    )
    (net (code "128") (name "Net-(U2-C)") (class "Default")
      (node (ref "R130") (pin "2") (pinfunction "2_2") (pintype "passive"))
      (node (ref "U100") (pin "1") (pintype "passive"))
      (node (ref "U2") (pin "4") (pinfunction "C_4") (pintype "passive"))
    )
    (net (code "129") (name "Net-(U3-CIN)") (class "Default")
      (node (ref "C17") (pin "1") (pinfunction "1_1") (pintype "passive"))
      (node (ref "J7") (pin "1") (pinfunction "1_1") (pintype "passive"))
      (node (ref "J7") (pin "2") (pinfunction "2_2") (pintype "passive"))
      (node (ref "R101") (pin "1") (pinfunction "1_1") (pintype "passive"))
      (node (ref "U3") (pin "15") (pinfunction "CIN_15") (pintype "passive"))
    )
    (net (code "130") (name "Net-(U3-VOT)") (class "Default")
      (node (ref "R3") (pin "1") (pinfunction "1_1") (pintype "passive"))
      (node (ref "U3") (pin "17") (pinfunction "VOT_17") (pintype "passive"))
    )
    (net (code "131") (name "Net-(U3-VUFB)") (class "Default")
      (node (ref "C12") (pin "2") (pinfunction "2_2") (pintype "passive"))
      (node (ref "C8") (pin "2") (pinfunction "2_2") (pintype "passive"))
      (node (ref "U3") (pin "2") (pinfunction "VUFB_2") (pintype "passive"))
    )
    (net (code "132") (name "Net-(U3-VVFB)") (class "Default")
      (node (ref "C1") (pin "2") (pinfunction "2_2") (pintype "passive"))
      (node (ref "C2") (pin "1") (pinfunction "1_1") (pintype "passive"))
      (node (ref "U3") (pin "3") (pinfunction "VVFB_3") (pintype "passive"))
    )
    (net (code "133") (name "Net-(U3-VWFB)") (class "Default")
      (node (ref "C3") (pin "1") (pinfunction "1_1") (pintype "passive"))
      (node (ref "C4") (pin "2") (pinfunction "2_2") (pintype "passive"))
      (node (ref "U3") (pin "4") (pinfunction "VWFB_4") (pintype "passive"))
    )
    (net (code "134") (name "Net-(U4-A)") (class "Default")
      (node (ref "C56") (pin "2") (pinfunction "2_2") (pintype "passive"))
      (node (ref "R69") (pin "2") (pinfunction "2_2") (pintype "passive"))
      (node (ref "R73") (pin "2") (pinfunction "2_2") (pintype "passive"))
      (node (ref "U4") (pin "1") (pinfunction "A_1") (pintype "passive"))
    )
    (net (code "135") (name "Net-(U4-C)") (class "Default")
      (node (ref "C53") (pin "2") (pinfunction "2_2") (pintype "passive"))
      (node (ref "D9") (pin "2") (pinfunction "2_2") (pintype "passive"))
      (node (ref "R72") (pin "2") (pinfunction "2_2") (pintype "passive"))
      (node (ref "U4") (pin "4") (pinfunction "C_4") (pintype "passive"))
    )
    (net (code "136") (name "Net-(U5-A)") (class "Default")
      (node (ref "D1") (pin "2") (pinfunction "2_2") (pintype "passive"))
      (node (ref "R64") (pin "2") (pinfunction "2_2") (pintype "passive"))
      (node (ref "U5") (pin "1") (pinfunction "A_1") (pintype "passive"))
    )
    (net (code "137") (name "Net-(U6-3IN-)") (class "Default")
      (node (ref "U6") (pin "8") (pinfunction "3OUT_8") (pintype "passive"))
      (node (ref "U6") (pin "9") (pinfunction "3IN-_9") (pintype "passive"))
    )
    (net (code "138") (name "Net-(U6-4IN-)") (class "Default")
      (node (ref "U6") (pin "13") (pinfunction "4IN-_13") (pintype "passive"))
      (node (ref "U6") (pin "14") (pinfunction "4OUT_14") (pintype "passive"))
    )
    (net (code "139") (name "Net-(U101-C.I.I.)") (class "Default")
      (node (ref "R105") (pin "1") (pinfunction "1_1") (pintype "passive"))
      (node (ref "R106") (pin "2") (pinfunction "2_2") (pintype "passive"))
      (node (ref "U101") (pin "5") (pinfunction "C.I.I._5") (pintype "passive"))
    )
    (net (code "140") (name "Net-(U101-D.C.)") (class "Default")
      (node (ref "R104") (pin "2") (pinfunction "2_2") (pintype "passive"))
      (node (ref "U101") (pin "1") (pinfunction "S.C._1") (pintype "passive"))
      (node (ref "U101") (pin "7") (pinfunction "Ipk_sense_7") (pintype "passive"))
      (node (ref "U101") (pin "8") (pinfunction "D.C._8") (pintype "power_in"))
    )
    (net (code "141") (name "Net-(U101-T.C.)") (class "Default")
      (node (ref "C109") (pin "1") (pinfunction "1_1") (pintype "passive"))
      (node (ref "U101") (pin "3") (pinfunction "T.C._3") (pintype "passive"))
    )
    (net (code "142") (name "P") (class "Default")
      (node (ref "BD1") (pin "4") (pinfunction "V+_4") (pintype "passive"))
      (node (ref "C13") (pin "2") (pinfunction "2_2") (pintype "passive"))
      (node (ref "C162") (pin "1") (pinfunction "1_1") (pintype "passive"))
      (node (ref "C5") (pin "1") (pinfunction "1_1") (pintype "passive"))
      (node (ref "DZ66") (pin "1") (pinfunction "A_1") (pintype "passive"))
      (node (ref "R310") (pin "1") (pinfunction "1_1") (pintype "passive"))
      (node (ref "R49") (pin "2") (pinfunction "2_2") (pintype "passive"))
      (node (ref "T1") (pin "1") (pinfunction "1_1") (pintype "passive"))
      (node (ref "U3") (pin "24") (pinfunction "P_24") (pintype "passive"))
    )
    (net (code "143") (name "UGND") (class "Default")
      (node (ref "C162") (pin "2") (pinfunction "2_2") (pintype "passive"))
      (node (ref "C163") (pin "2") (pinfunction "2_2") (pintype "passive"))
      (node (ref "C168") (pin "2") (pinfunction "2_2") (pintype "passive"))
      (node (ref "C53") (pin "1") (pinfunction "1_1") (pintype "passive"))
      (node (ref "C61") (pin "2") (pinfunction "2_2") (pintype "passive"))
      (node (ref "CN4") (pin "1") (pinfunction "1_1") (pintype "passive"))
      (node (ref "D1") (pin "1") (pinfunction "1_1") (pintype "passive"))
      (node (ref "D9") (pin "1") (pinfunction "1_1") (pintype "passive"))
      (node (ref "R35") (pin "1") (pinfunction "1_1") (pintype "passive"))
      (node (ref "R92") (pin "1") (pinfunction "1_1") (pintype "passive"))
      (node (ref "T1") (pin "9") (pinfunction "9_9") (pintype "passive"))
      (node (ref "U2") (pin "2") (pinfunction "K_2") (pintype "passive"))
      (node (ref "U4") (pin "3") (pinfunction "E_3") (pintype "passive"))
      (node (ref "U5") (pin "2") (pinfunction "K_2") (pintype "passive"))
    )
    (net (code "145") (name "unconnected-(CN1-Pad3)") (class "Default")
      (node (ref "CN1") (pin "3") (pinfunction "3_3") (pintype "passive"))
    )
    (net (code "146") (name "unconnected-(IC2-PA11-Pad29)") (class "Default")
      (node (ref "IC2") (pin "29") (pinfunction "PA11_29") (pintype "passive"))
    )
    (net (code "147") (name "unconnected-(IC2-PA12-Pad30)") (class "Default")
      (node (ref "IC2") (pin "30") (pinfunction "PA12_30") (pintype "passive"))
    )
    (net (code "148") (name "unconnected-(IC2-PA15-Pad35)") (class "Default")
      (node (ref "IC2") (pin "35") (pinfunction "PA15_35") (pintype "passive"))
    )
    (net (code "149") (name "unconnected-(IC2-PB15-Pad25)") (class "Default")
      (node (ref "IC2") (pin "25") (pinfunction "PB15_25") (pintype "passive"))
    )
    (net (code "150") (name "unconnected-(IC2-XTLI{slash}PC14-Pad2)") (class "Default")
      (node (ref "IC2") (pin "2") (pinfunction "XTLI/PC14_2") (pintype "passive"))
    )
    (net (code "151") (name "unconnected-(IC2-XTLO{slash}PC15-Pad3)") (class "Default")
      (node (ref "IC2") (pin "3") (pinfunction "XTLO/PC15_3") (pintype "passive"))
    )
    (net (code "152") (name "unconnected-(U3-NC-Pad1)") (class "Default")
      (node (ref "U3") (pin "1") (pinfunction "NC_1") (pintype "passive"))
    )
    (net (code "153") (name "unconnected-(U3-NC-Pad13)") (class "Default")
      (node (ref "U3") (pin "13") (pinfunction "NC_13") (pintype "passive"))
    )
    (net (code "154") (name "unconnected-(U3-NC-Pad25)") (class "Default")
      (node (ref "U3") (pin "25") (pinfunction "NC_25") (pintype "passive"))
    )
  )
)
